# coBWeb.net
KiCad netlist of a schematic drawn in EasyEDA Pro
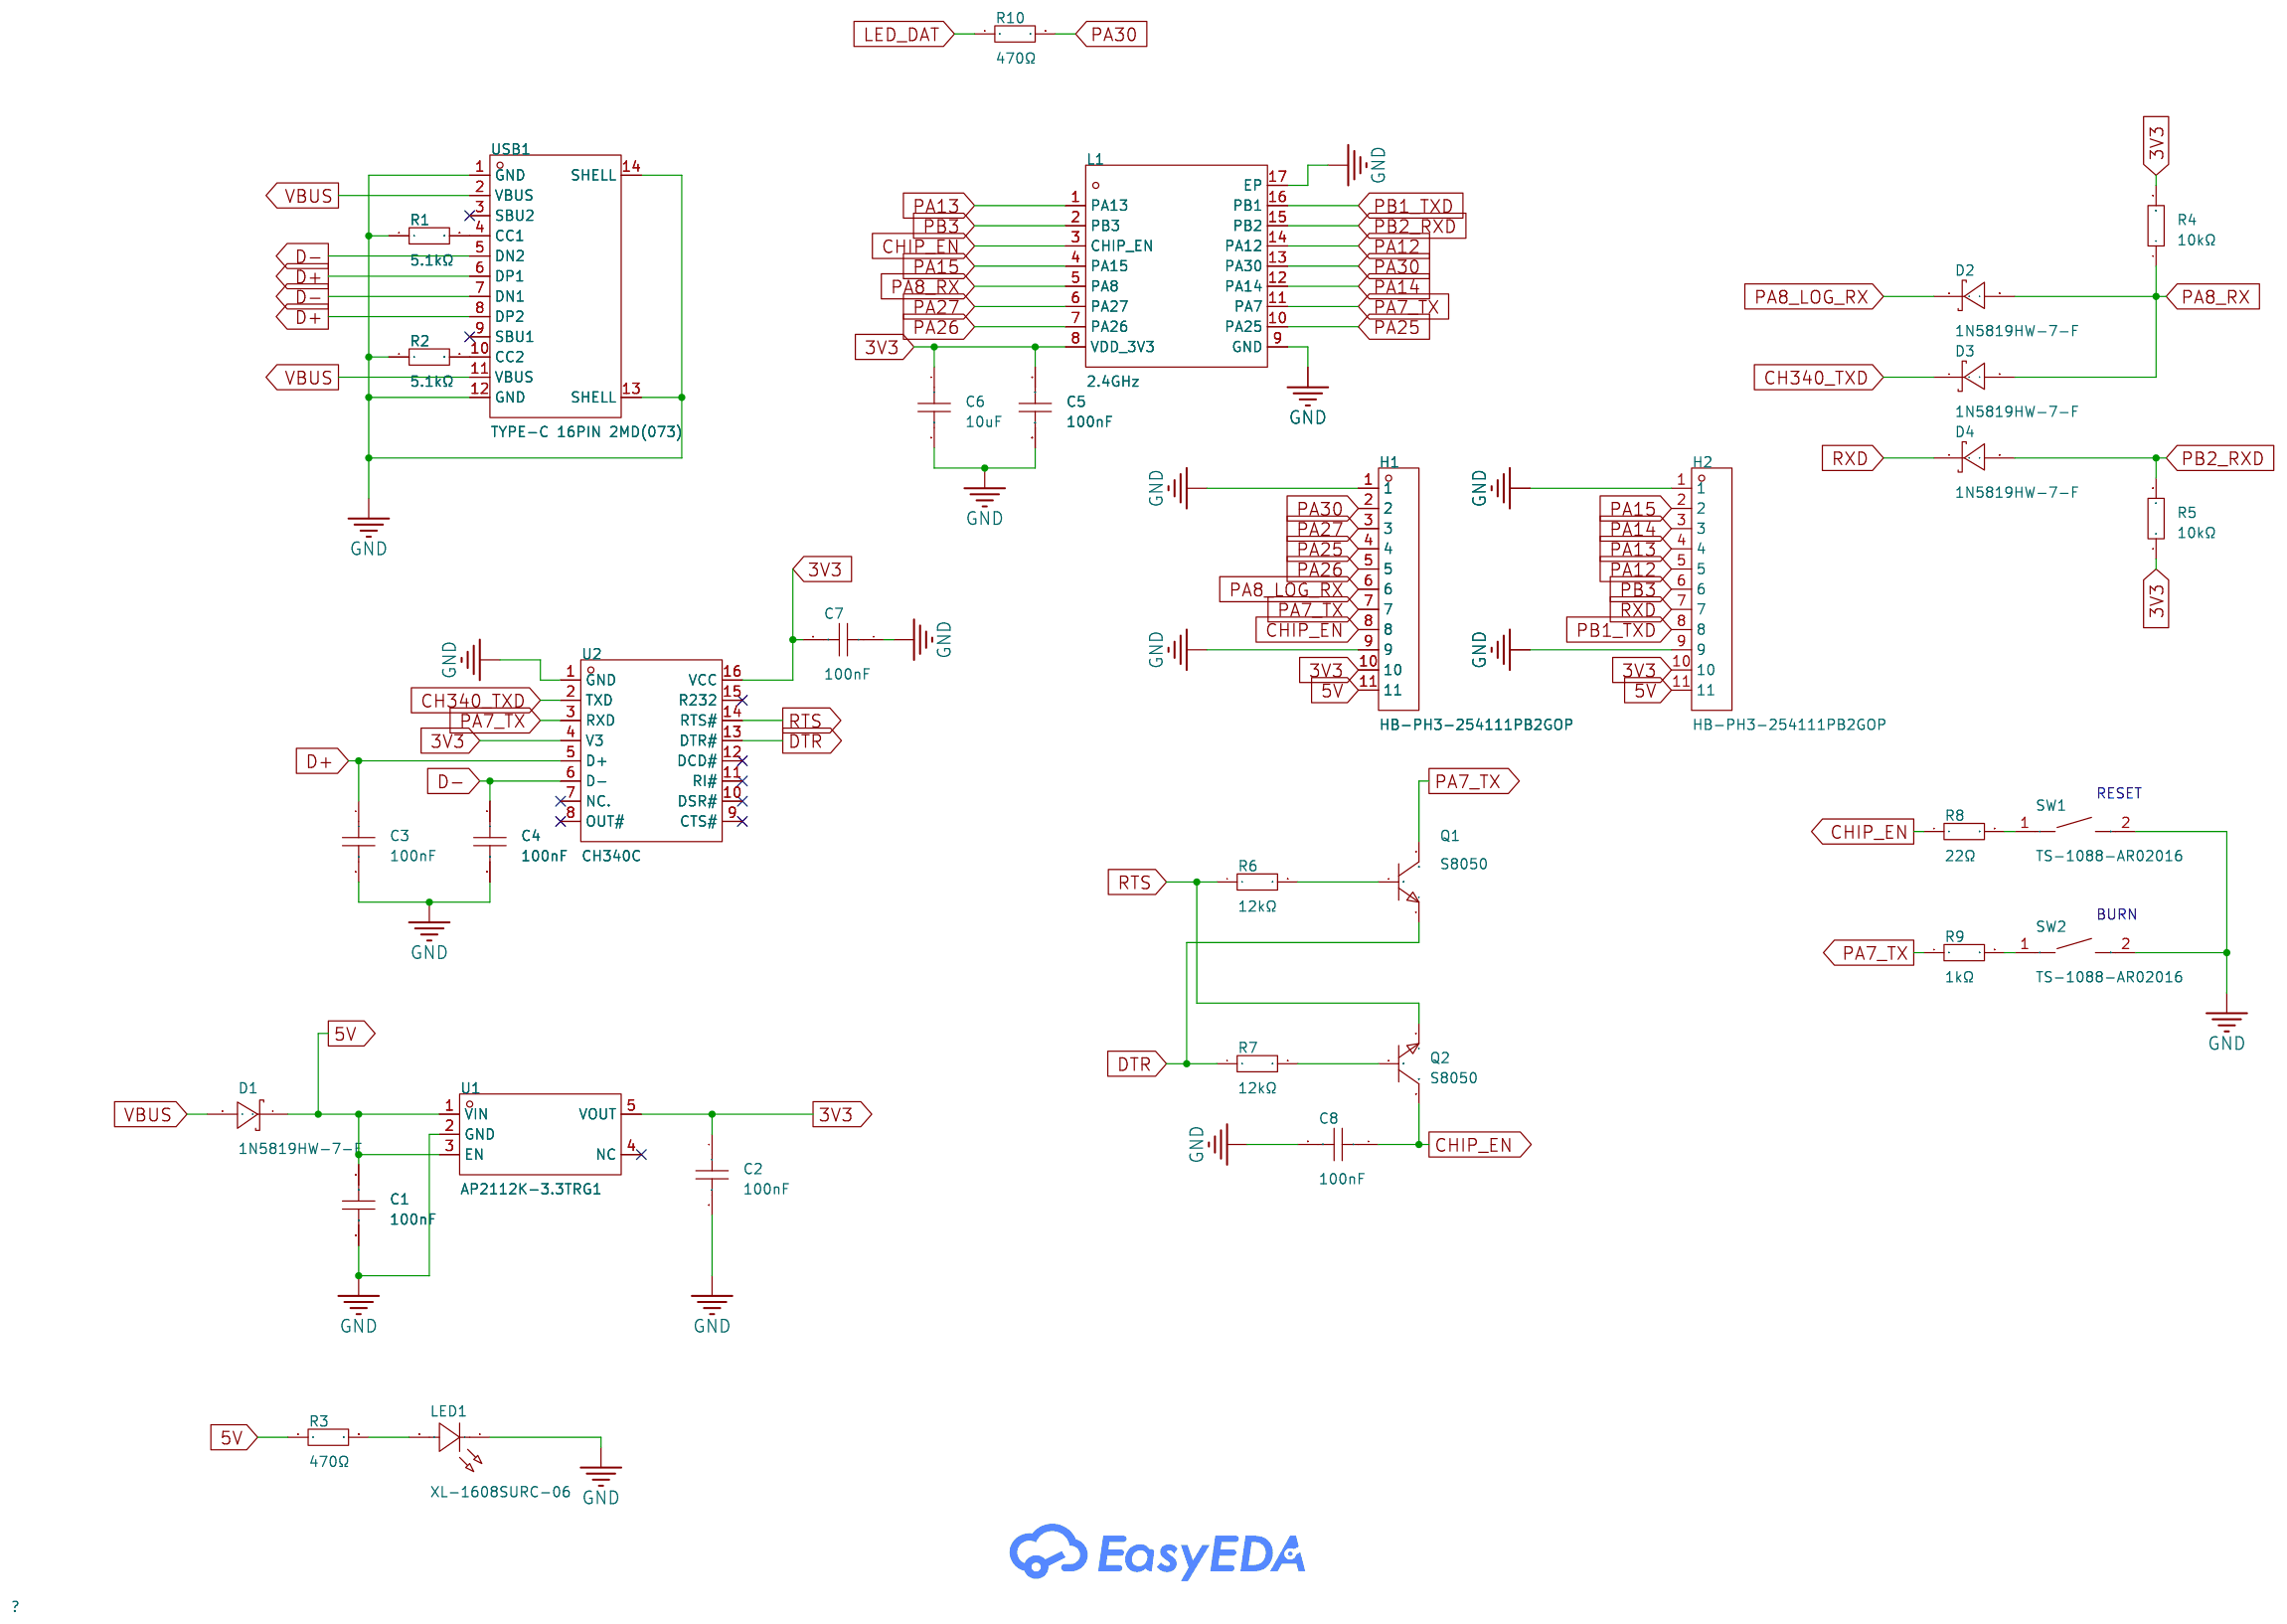
[diagram p0: P1]
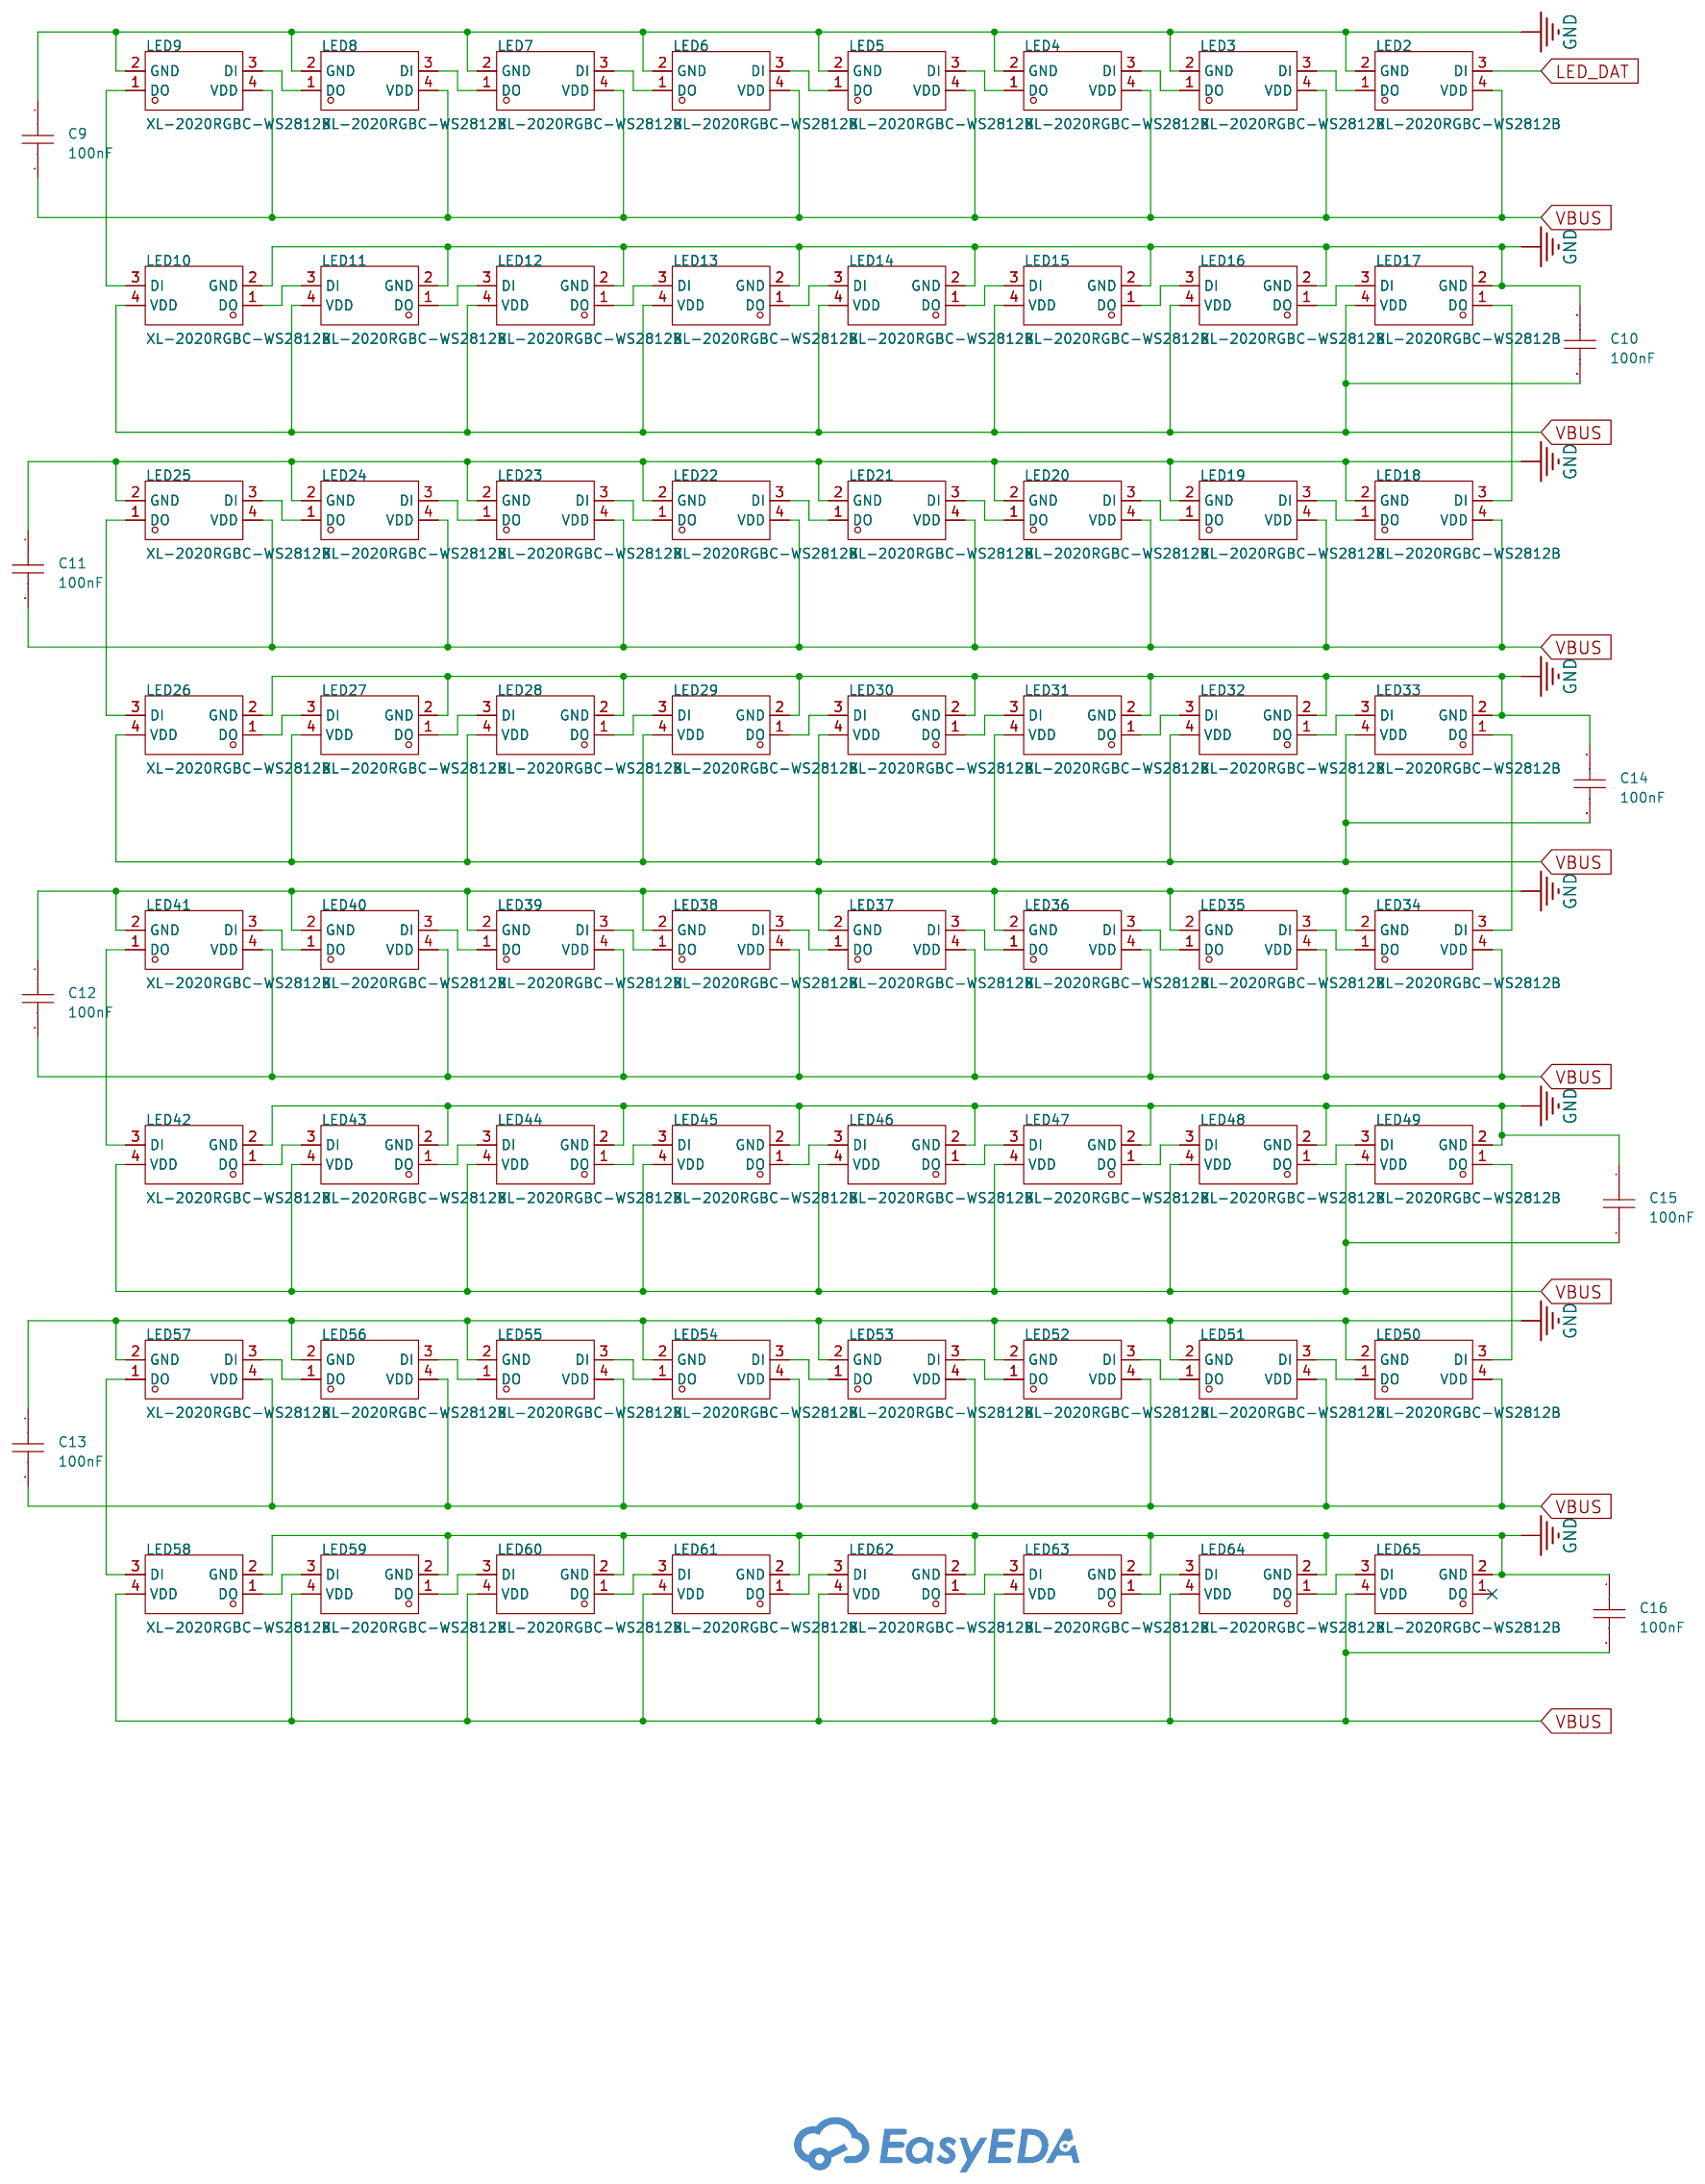
[diagram p1: P2]

(export (version "E")
  (design (tool "Eeschema 10.0.6"))
  (components
    (comp (ref "C1")
      (value "100nF")
      (footprint "easyedapro:C0603")
      (fields
        (field (name "Manufacturer Part") "CGA0402X7R104K160GT")
        (field (name "Manufacturer") "HRE(芯声)")
      )
      (libsource (lib "easyedapro") (part "CAP"))
    )
    (comp (ref "C2")
      (value "100nF")
      (footprint "easyedapro:C0603")
      (fields
        (field (name "Manufacturer Part") "CGA0402X7R104K160GT")
        (field (name "Manufacturer") "HRE(芯声)")
      )
      (libsource (lib "easyedapro") (part "CAP"))
    )
    (comp (ref "C3")
      (value "100nF")
      (footprint "easyedapro:C0603")
      (fields
        (field (name "Manufacturer Part") "CGA0402X7R104K160GT")
        (field (name "Manufacturer") "HRE(芯声)")
      )
      (libsource (lib "easyedapro") (part "CAP"))
    )
    (comp (ref "C4")
      (value "100nF")
      (footprint "easyedapro:C0603")
      (fields
        (field (name "Manufacturer Part") "CGA0402X7R104K160GT")
        (field (name "Manufacturer") "HRE(芯声)")
      )
      (libsource (lib "easyedapro") (part "CAP"))
    )
    (comp (ref "C5")
      (value "100nF")
      (footprint "easyedapro:C0603")
      (fields
        (field (name "Manufacturer Part") "CGA0402X7R104K160GT")
        (field (name "Manufacturer") "HRE(芯声)")
      )
      (libsource (lib "easyedapro") (part "CAP"))
    )
    (comp (ref "C6")
      (value "10uF")
      (footprint "easyedapro:C0603")
      (fields
        (field (name "Manufacturer Part") "GRM155R60J106ME44D")
        (field (name "Manufacturer") "muRata(村田)")
      )
      (libsource (lib "easyedapro") (part "CAP"))
    )
    (comp (ref "C7")
      (value "100nF")
      (footprint "easyedapro:C0603")
      (fields
        (field (name "Manufacturer Part") "CGA0402X7R104K160GT")
        (field (name "Manufacturer") "HRE(芯声)")
      )
      (libsource (lib "easyedapro") (part "CAP"))
    )
    (comp (ref "C8")
      (value "100nF")
      (footprint "easyedapro:C0603")
      (fields
        (field (name "Manufacturer Part") "CGA0402X7R104K160GT")
        (field (name "Manufacturer") "HRE(芯声)")
      )
      (libsource (lib "easyedapro") (part "CAP"))
    )
    (comp (ref "D1")
      (value "1N5819HW-7-F")
      (footprint "easyedapro:SOD-123_L2.7-W1.6-LS3.7-RD")
      (fields (field (name "Manufacturer") "DIODES(美台)"))
      (libsource (lib "easyedapro") (part "1N5819HW-7-F"))
    )
    (comp (ref "D2")
      (value "1N5819HW-7-F")
      (footprint "easyedapro:SOD-123_L2.7-W1.6-LS3.7-RD")
      (fields (field (name "Manufacturer") "DIODES(美台)"))
      (libsource (lib "easyedapro") (part "1N5819HW-7-F"))
    )
    (comp (ref "D3")
      (value "1N5819HW-7-F")
      (footprint "easyedapro:SOD-123_L2.7-W1.6-LS3.7-RD")
      (fields (field (name "Manufacturer") "DIODES(美台)"))
      (libsource (lib "easyedapro") (part "1N5819HW-7-F"))
    )
    (comp (ref "D4")
      (value "1N5819HW-7-F")
      (footprint "easyedapro:SOD-123_L2.7-W1.6-LS3.7-RD")
      (fields (field (name "Manufacturer") "DIODES(美台)"))
      (libsource (lib "easyedapro") (part "1N5819HW-7-F"))
    )
    (comp (ref "H1")
      (value "HB-PH3-254111PB2GOP")
      (footprint "easyedapro:HDR-TH_11P-P2.54-V-M")
      (fields (field (name "Manufacturer") "HANBO(汉博)"))
      (libsource (lib "easyedapro") (part "HB-PH3-254111PB2GOP"))
    )
    (comp (ref "H2")
      (value "HB-PH3-254111PB2GOP")
      (footprint "easyedapro:HDR-TH_11P-P2.54-V-M")
      (fields (field (name "Manufacturer") "HANBO(汉博)"))
      (libsource (lib "easyedapro") (part "HB-PH3-254111PB2GOP"))
    )
    (comp (ref "L1")
      (value "2.4GHz")
      (footprint "easyedapro:WIFI-SMD_BW16")
      (fields (field (name "Manufacturer Part") "BW16") (field (name "Manufacturer") "Ai-Thinker(安信可)"))
      (libsource (lib "easyedapro") (part "BW16"))
    )
    (comp (ref "LED1")
      (value "XL-1608SURC-06")
      (footprint "easyedapro:LED0603-RD_RED")
      (fields (field (name "Manufacturer") "XINGLIGHT(成兴光)"))
      (libsource (lib "easyedapro") (part "XL-1608SURC-06"))
    )
    (comp (ref "Q1")
      (value "S8050")
      (footprint "easyedapro:SOT-23-3_L2.9-W1.3-P1.90-LS2.4-BR")
      (fields (field (name "Manufacturer") "JSMSEMI(杰盛微)"))
      (libsource (lib "easyedapro") (part "S8050"))
    )
    (comp (ref "Q2")
      (value "S8050")
      (footprint "easyedapro:SOT-23-3_L2.9-W1.3-P1.90-LS2.4-BR")
      (fields (field (name "Manufacturer") "JSMSEMI(杰盛微)"))
      (libsource (lib "easyedapro") (part "S8050"))
    )
    (comp (ref "R1")
      (value "5.1kΩ")
      (footprint "easyedapro:R0603")
      (fields
        (field (name "Manufacturer Part") "0402WGF5101TCE")
        (field (name "Manufacturer") "UNI-ROYAL(厚声)")
      )
      (libsource (lib "easyedapro") (part "Res"))
    )
    (comp (ref "R2")
      (value "5.1kΩ")
      (footprint "easyedapro:R0603")
      (fields
        (field (name "Manufacturer Part") "0402WGF5101TCE")
        (field (name "Manufacturer") "UNI-ROYAL(厚声)")
      )
      (libsource (lib "easyedapro") (part "Res"))
    )
    (comp (ref "R3")
      (value "470Ω")
      (footprint "easyedapro:R0603")
      (fields (field (name "Manufacturer Part") "RC0402FR-07470RL") (field (name "Manufacturer") "YAGEO(国巨)"))
      (libsource (lib "easyedapro") (part "Res"))
    )
    (comp (ref "R4")
      (value "10kΩ")
      (footprint "easyedapro:R0603")
      (fields
        (field (name "Manufacturer Part") "0402WGF1002TCE")
        (field (name "Manufacturer") "UNI-ROYAL(厚声)")
      )
      (libsource (lib "easyedapro") (part "Res"))
    )
    (comp (ref "R5")
      (value "10kΩ")
      (footprint "easyedapro:R0603")
      (fields
        (field (name "Manufacturer Part") "0402WGF1002TCE")
        (field (name "Manufacturer") "UNI-ROYAL(厚声)")
      )
      (libsource (lib "easyedapro") (part "Res"))
    )
    (comp (ref "R6")
      (value "12kΩ")
      (footprint "easyedapro:R0603")
      (fields (field (name "Manufacturer Part") "RTT021202FTH") (field (name "Manufacturer") "RALEC(旺诠)"))
      (libsource (lib "easyedapro") (part "Res"))
    )
    (comp (ref "R7")
      (value "12kΩ")
      (footprint "easyedapro:R0603")
      (fields (field (name "Manufacturer Part") "RTT021202FTH") (field (name "Manufacturer") "RALEC(旺诠)"))
      (libsource (lib "easyedapro") (part "Res"))
    )
    (comp (ref "R8")
      (value "22Ω")
      (footprint "easyedapro:R0603")
      (fields
        (field (name "Manufacturer Part") "0402WGF220JTCE")
        (field (name "Manufacturer") "UNI-ROYAL(厚声)")
      )
      (libsource (lib "easyedapro") (part "Res"))
    )
    (comp (ref "R9")
      (value "1kΩ")
      (footprint "easyedapro:R0603")
      (fields
        (field (name "Manufacturer Part") "0402WGF1001TCE")
        (field (name "Manufacturer") "UNI-ROYAL(厚声)")
      )
      (libsource (lib "easyedapro") (part "Res"))
    )
    (comp (ref "R10")
      (value "470Ω")
      (footprint "easyedapro:R0603")
      (fields (field (name "Manufacturer Part") "RC0402FR-07470RL") (field (name "Manufacturer") "YAGEO(国巨)"))
      (libsource (lib "easyedapro") (part "Res"))
    )
    (comp (ref "SW1")
      (value "TS-1088-AR02016")
      (footprint "easyedapro:SW-SMD_L3.9-W3.0-P4.45")
      (fields (field (name "Manufacturer") "XUNPU(讯普)"))
      (libsource (lib "easyedapro") (part "TS-1088-AR02016"))
    )
    (comp (ref "SW2")
      (value "TS-1088-AR02016")
      (footprint "easyedapro:SW-SMD_L3.9-W3.0-P4.45")
      (fields (field (name "Manufacturer") "XUNPU(讯普)"))
      (libsource (lib "easyedapro") (part "TS-1088-AR02016"))
    )
    (comp (ref "U1")
      (value "AP2112K-3.3TRG1")
      (footprint "easyedapro:SOT-25-5_L2.9-W1.6-P0.95-LS2.8-BL")
      (fields (field (name "Manufacturer") "DIODES(美台)"))
      (libsource (lib "easyedapro") (part "AP2112K-3.3TRG1"))
    )
    (comp (ref "U2")
      (value "CH340C")
      (footprint "easyedapro:SOP-16_L10.0-W3.9-P1.27-LS6.0-BL")
      (fields (field (name "Manufacturer") "WCH(南京沁恒)"))
      (libsource (lib "easyedapro") (part "CH340C"))
    )
    (comp (ref "USB1")
      (value "TYPE-C 16PIN 2MD(073)")
      (footprint "easyedapro:USB-C-SMD_TYPE-C-6PIN-2MD-073")
      (fields (field (name "Manufacturer") "SHOU HAN(首韩)"))
      (libsource (lib "easyedapro") (part "TYPE-C 16PIN 2MD(073)"))
    )
    (comp (ref "C9")
      (value "100nF")
      (footprint "easyedapro:C0603")
      (fields
        (field (name "Manufacturer Part") "CGA0402X7R104K160GT")
        (field (name "Manufacturer") "HRE(芯声)")
      )
      (libsource (lib "easyedapro") (part "CAP"))
    )
    (comp (ref "C10")
      (value "100nF")
      (footprint "easyedapro:C0603")
      (fields
        (field (name "Manufacturer Part") "CGA0402X7R104K160GT")
        (field (name "Manufacturer") "HRE(芯声)")
      )
      (libsource (lib "easyedapro") (part "CAP"))
    )
    (comp (ref "C11")
      (value "100nF")
      (footprint "easyedapro:C0603")
      (fields
        (field (name "Manufacturer Part") "CGA0402X7R104K160GT")
        (field (name "Manufacturer") "HRE(芯声)")
      )
      (libsource (lib "easyedapro") (part "CAP"))
    )
    (comp (ref "C12")
      (value "100nF")
      (footprint "easyedapro:C0603")
      (fields
        (field (name "Manufacturer Part") "CGA0402X7R104K160GT")
        (field (name "Manufacturer") "HRE(芯声)")
      )
      (libsource (lib "easyedapro") (part "CAP"))
    )
    (comp (ref "C13")
      (value "100nF")
      (footprint "easyedapro:C0603")
      (fields
        (field (name "Manufacturer Part") "CGA0402X7R104K160GT")
        (field (name "Manufacturer") "HRE(芯声)")
      )
      (libsource (lib "easyedapro") (part "CAP"))
    )
    (comp (ref "C14")
      (value "100nF")
      (footprint "easyedapro:C0603")
      (fields
        (field (name "Manufacturer Part") "CGA0402X7R104K160GT")
        (field (name "Manufacturer") "HRE(芯声)")
      )
      (libsource (lib "easyedapro") (part "CAP"))
    )
    (comp (ref "C15")
      (value "100nF")
      (footprint "easyedapro:C0603")
      (fields
        (field (name "Manufacturer Part") "CGA0402X7R104K160GT")
        (field (name "Manufacturer") "HRE(芯声)")
      )
      (libsource (lib "easyedapro") (part "CAP"))
    )
    (comp (ref "C16")
      (value "100nF")
      (footprint "easyedapro:C0603")
      (fields
        (field (name "Manufacturer Part") "CGA0402X7R104K160GT")
        (field (name "Manufacturer") "HRE(芯声)")
      )
      (libsource (lib "easyedapro") (part "CAP"))
    )
    (comp (ref "LED2")
      (value "XL-2020RGBC-WS2812B")
      (footprint "easyedapro:LED-SMD_4P-L2.0-W2.0-BR-1")
      (fields (field (name "Manufacturer") "XINGLIGHT(成兴光)"))
      (libsource (lib "easyedapro") (part "XL-2020RGBC-WS2812B"))
    )
    (comp (ref "LED3")
      (value "XL-2020RGBC-WS2812B")
      (footprint "easyedapro:LED-SMD_4P-L2.0-W2.0-BR-1")
      (fields (field (name "Manufacturer") "XINGLIGHT(成兴光)"))
      (libsource (lib "easyedapro") (part "XL-2020RGBC-WS2812B"))
    )
    (comp (ref "LED4")
      (value "XL-2020RGBC-WS2812B")
      (footprint "easyedapro:LED-SMD_4P-L2.0-W2.0-BR-1")
      (fields (field (name "Manufacturer") "XINGLIGHT(成兴光)"))
      (libsource (lib "easyedapro") (part "XL-2020RGBC-WS2812B"))
    )
    (comp (ref "LED5")
      (value "XL-2020RGBC-WS2812B")
      (footprint "easyedapro:LED-SMD_4P-L2.0-W2.0-BR-1")
      (fields (field (name "Manufacturer") "XINGLIGHT(成兴光)"))
      (libsource (lib "easyedapro") (part "XL-2020RGBC-WS2812B"))
    )
    (comp (ref "LED6")
      (value "XL-2020RGBC-WS2812B")
      (footprint "easyedapro:LED-SMD_4P-L2.0-W2.0-BR-1")
      (fields (field (name "Manufacturer") "XINGLIGHT(成兴光)"))
      (libsource (lib "easyedapro") (part "XL-2020RGBC-WS2812B"))
    )
    (comp (ref "LED7")
      (value "XL-2020RGBC-WS2812B")
      (footprint "easyedapro:LED-SMD_4P-L2.0-W2.0-BR-1")
      (fields (field (name "Manufacturer") "XINGLIGHT(成兴光)"))
      (libsource (lib "easyedapro") (part "XL-2020RGBC-WS2812B"))
    )
    (comp (ref "LED8")
      (value "XL-2020RGBC-WS2812B")
      (footprint "easyedapro:LED-SMD_4P-L2.0-W2.0-BR-1")
      (fields (field (name "Manufacturer") "XINGLIGHT(成兴光)"))
      (libsource (lib "easyedapro") (part "XL-2020RGBC-WS2812B"))
    )
    (comp (ref "LED9")
      (value "XL-2020RGBC-WS2812B")
      (footprint "easyedapro:LED-SMD_4P-L2.0-W2.0-BR-1")
      (fields (field (name "Manufacturer") "XINGLIGHT(成兴光)"))
      (libsource (lib "easyedapro") (part "XL-2020RGBC-WS2812B"))
    )
    (comp (ref "LED10")
      (value "XL-2020RGBC-WS2812B")
      (footprint "easyedapro:LED-SMD_4P-L2.0-W2.0-BR-1")
      (fields (field (name "Manufacturer") "XINGLIGHT(成兴光)"))
      (libsource (lib "easyedapro") (part "XL-2020RGBC-WS2812B"))
    )
    (comp (ref "LED11")
      (value "XL-2020RGBC-WS2812B")
      (footprint "easyedapro:LED-SMD_4P-L2.0-W2.0-BR-1")
      (fields (field (name "Manufacturer") "XINGLIGHT(成兴光)"))
      (libsource (lib "easyedapro") (part "XL-2020RGBC-WS2812B"))
    )
    (comp (ref "LED12")
      (value "XL-2020RGBC-WS2812B")
      (footprint "easyedapro:LED-SMD_4P-L2.0-W2.0-BR-1")
      (fields (field (name "Manufacturer") "XINGLIGHT(成兴光)"))
      (libsource (lib "easyedapro") (part "XL-2020RGBC-WS2812B"))
    )
    (comp (ref "LED13")
      (value "XL-2020RGBC-WS2812B")
      (footprint "easyedapro:LED-SMD_4P-L2.0-W2.0-BR-1")
      (fields (field (name "Manufacturer") "XINGLIGHT(成兴光)"))
      (libsource (lib "easyedapro") (part "XL-2020RGBC-WS2812B"))
    )
    (comp (ref "LED14")
      (value "XL-2020RGBC-WS2812B")
      (footprint "easyedapro:LED-SMD_4P-L2.0-W2.0-BR-1")
      (fields (field (name "Manufacturer") "XINGLIGHT(成兴光)"))
      (libsource (lib "easyedapro") (part "XL-2020RGBC-WS2812B"))
    )
    (comp (ref "LED15")
      (value "XL-2020RGBC-WS2812B")
      (footprint "easyedapro:LED-SMD_4P-L2.0-W2.0-BR-1")
      (fields (field (name "Manufacturer") "XINGLIGHT(成兴光)"))
      (libsource (lib "easyedapro") (part "XL-2020RGBC-WS2812B"))
    )
    (comp (ref "LED16")
      (value "XL-2020RGBC-WS2812B")
      (footprint "easyedapro:LED-SMD_4P-L2.0-W2.0-BR-1")
      (fields (field (name "Manufacturer") "XINGLIGHT(成兴光)"))
      (libsource (lib "easyedapro") (part "XL-2020RGBC-WS2812B"))
    )
    (comp (ref "LED17")
      (value "XL-2020RGBC-WS2812B")
      (footprint "easyedapro:LED-SMD_4P-L2.0-W2.0-BR-1")
      (fields (field (name "Manufacturer") "XINGLIGHT(成兴光)"))
      (libsource (lib "easyedapro") (part "XL-2020RGBC-WS2812B"))
    )
    (comp (ref "LED18")
      (value "XL-2020RGBC-WS2812B")
      (footprint "easyedapro:LED-SMD_4P-L2.0-W2.0-BR-1")
      (fields (field (name "Manufacturer") "XINGLIGHT(成兴光)"))
      (libsource (lib "easyedapro") (part "XL-2020RGBC-WS2812B"))
    )
    (comp (ref "LED19")
      (value "XL-2020RGBC-WS2812B")
      (footprint "easyedapro:LED-SMD_4P-L2.0-W2.0-BR-1")
      (fields (field (name "Manufacturer") "XINGLIGHT(成兴光)"))
      (libsource (lib "easyedapro") (part "XL-2020RGBC-WS2812B"))
    )
    (comp (ref "LED20")
      (value "XL-2020RGBC-WS2812B")
      (footprint "easyedapro:LED-SMD_4P-L2.0-W2.0-BR-1")
      (fields (field (name "Manufacturer") "XINGLIGHT(成兴光)"))
      (libsource (lib "easyedapro") (part "XL-2020RGBC-WS2812B"))
    )
    (comp (ref "LED21")
      (value "XL-2020RGBC-WS2812B")
      (footprint "easyedapro:LED-SMD_4P-L2.0-W2.0-BR-1")
      (fields (field (name "Manufacturer") "XINGLIGHT(成兴光)"))
      (libsource (lib "easyedapro") (part "XL-2020RGBC-WS2812B"))
    )
    (comp (ref "LED22")
      (value "XL-2020RGBC-WS2812B")
      (footprint "easyedapro:LED-SMD_4P-L2.0-W2.0-BR-1")
      (fields (field (name "Manufacturer") "XINGLIGHT(成兴光)"))
      (libsource (lib "easyedapro") (part "XL-2020RGBC-WS2812B"))
    )
    (comp (ref "LED23")
      (value "XL-2020RGBC-WS2812B")
      (footprint "easyedapro:LED-SMD_4P-L2.0-W2.0-BR-1")
      (fields (field (name "Manufacturer") "XINGLIGHT(成兴光)"))
      (libsource (lib "easyedapro") (part "XL-2020RGBC-WS2812B"))
    )
    (comp (ref "LED24")
      (value "XL-2020RGBC-WS2812B")
      (footprint "easyedapro:LED-SMD_4P-L2.0-W2.0-BR-1")
      (fields (field (name "Manufacturer") "XINGLIGHT(成兴光)"))
      (libsource (lib "easyedapro") (part "XL-2020RGBC-WS2812B"))
    )
    (comp (ref "LED25")
      (value "XL-2020RGBC-WS2812B")
      (footprint "easyedapro:LED-SMD_4P-L2.0-W2.0-BR-1")
      (fields (field (name "Manufacturer") "XINGLIGHT(成兴光)"))
      (libsource (lib "easyedapro") (part "XL-2020RGBC-WS2812B"))
    )
    (comp (ref "LED26")
      (value "XL-2020RGBC-WS2812B")
      (footprint "easyedapro:LED-SMD_4P-L2.0-W2.0-BR-1")
      (fields (field (name "Manufacturer") "XINGLIGHT(成兴光)"))
      (libsource (lib "easyedapro") (part "XL-2020RGBC-WS2812B"))
    )
    (comp (ref "LED27")
      (value "XL-2020RGBC-WS2812B")
      (footprint "easyedapro:LED-SMD_4P-L2.0-W2.0-BR-1")
      (fields (field (name "Manufacturer") "XINGLIGHT(成兴光)"))
      (libsource (lib "easyedapro") (part "XL-2020RGBC-WS2812B"))
    )
    (comp (ref "LED28")
      (value "XL-2020RGBC-WS2812B")
      (footprint "easyedapro:LED-SMD_4P-L2.0-W2.0-BR-1")
      (fields (field (name "Manufacturer") "XINGLIGHT(成兴光)"))
      (libsource (lib "easyedapro") (part "XL-2020RGBC-WS2812B"))
    )
    (comp (ref "LED29")
      (value "XL-2020RGBC-WS2812B")
      (footprint "easyedapro:LED-SMD_4P-L2.0-W2.0-BR-1")
      (fields (field (name "Manufacturer") "XINGLIGHT(成兴光)"))
      (libsource (lib "easyedapro") (part "XL-2020RGBC-WS2812B"))
    )
    (comp (ref "LED30")
      (value "XL-2020RGBC-WS2812B")
      (footprint "easyedapro:LED-SMD_4P-L2.0-W2.0-BR-1")
      (fields (field (name "Manufacturer") "XINGLIGHT(成兴光)"))
      (libsource (lib "easyedapro") (part "XL-2020RGBC-WS2812B"))
    )
    (comp (ref "LED31")
      (value "XL-2020RGBC-WS2812B")
      (footprint "easyedapro:LED-SMD_4P-L2.0-W2.0-BR-1")
      (fields (field (name "Manufacturer") "XINGLIGHT(成兴光)"))
      (libsource (lib "easyedapro") (part "XL-2020RGBC-WS2812B"))
    )
    (comp (ref "LED32")
      (value "XL-2020RGBC-WS2812B")
      (footprint "easyedapro:LED-SMD_4P-L2.0-W2.0-BR-1")
      (fields (field (name "Manufacturer") "XINGLIGHT(成兴光)"))
      (libsource (lib "easyedapro") (part "XL-2020RGBC-WS2812B"))
    )
    (comp (ref "LED33")
      (value "XL-2020RGBC-WS2812B")
      (footprint "easyedapro:LED-SMD_4P-L2.0-W2.0-BR-1")
      (fields (field (name "Manufacturer") "XINGLIGHT(成兴光)"))
      (libsource (lib "easyedapro") (part "XL-2020RGBC-WS2812B"))
    )
    (comp (ref "LED34")
      (value "XL-2020RGBC-WS2812B")
      (footprint "easyedapro:LED-SMD_4P-L2.0-W2.0-BR-1")
      (fields (field (name "Manufacturer") "XINGLIGHT(成兴光)"))
      (libsource (lib "easyedapro") (part "XL-2020RGBC-WS2812B"))
    )
    (comp (ref "LED35")
      (value "XL-2020RGBC-WS2812B")
      (footprint "easyedapro:LED-SMD_4P-L2.0-W2.0-BR-1")
      (fields (field (name "Manufacturer") "XINGLIGHT(成兴光)"))
      (libsource (lib "easyedapro") (part "XL-2020RGBC-WS2812B"))
    )
    (comp (ref "LED36")
      (value "XL-2020RGBC-WS2812B")
      (footprint "easyedapro:LED-SMD_4P-L2.0-W2.0-BR-1")
      (fields (field (name "Manufacturer") "XINGLIGHT(成兴光)"))
      (libsource (lib "easyedapro") (part "XL-2020RGBC-WS2812B"))
    )
    (comp (ref "LED37")
      (value "XL-2020RGBC-WS2812B")
      (footprint "easyedapro:LED-SMD_4P-L2.0-W2.0-BR-1")
      (fields (field (name "Manufacturer") "XINGLIGHT(成兴光)"))
      (libsource (lib "easyedapro") (part "XL-2020RGBC-WS2812B"))
    )
    (comp (ref "LED38")
      (value "XL-2020RGBC-WS2812B")
      (footprint "easyedapro:LED-SMD_4P-L2.0-W2.0-BR-1")
      (fields (field (name "Manufacturer") "XINGLIGHT(成兴光)"))
      (libsource (lib "easyedapro") (part "XL-2020RGBC-WS2812B"))
    )
    (comp (ref "LED39")
      (value "XL-2020RGBC-WS2812B")
      (footprint "easyedapro:LED-SMD_4P-L2.0-W2.0-BR-1")
      (fields (field (name "Manufacturer") "XINGLIGHT(成兴光)"))
      (libsource (lib "easyedapro") (part "XL-2020RGBC-WS2812B"))
    )
    (comp (ref "LED40")
      (value "XL-2020RGBC-WS2812B")
      (footprint "easyedapro:LED-SMD_4P-L2.0-W2.0-BR-1")
      (fields (field (name "Manufacturer") "XINGLIGHT(成兴光)"))
      (libsource (lib "easyedapro") (part "XL-2020RGBC-WS2812B"))
    )
    (comp (ref "LED41")
      (value "XL-2020RGBC-WS2812B")
      (footprint "easyedapro:LED-SMD_4P-L2.0-W2.0-BR-1")
      (fields (field (name "Manufacturer") "XINGLIGHT(成兴光)"))
      (libsource (lib "easyedapro") (part "XL-2020RGBC-WS2812B"))
    )
    (comp (ref "LED42")
      (value "XL-2020RGBC-WS2812B")
      (footprint "easyedapro:LED-SMD_4P-L2.0-W2.0-BR-1")
      (fields (field (name "Manufacturer") "XINGLIGHT(成兴光)"))
      (libsource (lib "easyedapro") (part "XL-2020RGBC-WS2812B"))
    )
    (comp (ref "LED43")
      (value "XL-2020RGBC-WS2812B")
      (footprint "easyedapro:LED-SMD_4P-L2.0-W2.0-BR-1")
      (fields (field (name "Manufacturer") "XINGLIGHT(成兴光)"))
      (libsource (lib "easyedapro") (part "XL-2020RGBC-WS2812B"))
    )
    (comp (ref "LED44")
      (value "XL-2020RGBC-WS2812B")
      (footprint "easyedapro:LED-SMD_4P-L2.0-W2.0-BR-1")
      (fields (field (name "Manufacturer") "XINGLIGHT(成兴光)"))
      (libsource (lib "easyedapro") (part "XL-2020RGBC-WS2812B"))
    )
    (comp (ref "LED45")
      (value "XL-2020RGBC-WS2812B")
      (footprint "easyedapro:LED-SMD_4P-L2.0-W2.0-BR-1")
      (fields (field (name "Manufacturer") "XINGLIGHT(成兴光)"))
      (libsource (lib "easyedapro") (part "XL-2020RGBC-WS2812B"))
    )
    (comp (ref "LED46")
      (value "XL-2020RGBC-WS2812B")
      (footprint "easyedapro:LED-SMD_4P-L2.0-W2.0-BR-1")
      (fields (field (name "Manufacturer") "XINGLIGHT(成兴光)"))
      (libsource (lib "easyedapro") (part "XL-2020RGBC-WS2812B"))
    )
    (comp (ref "LED47")
      (value "XL-2020RGBC-WS2812B")
      (footprint "easyedapro:LED-SMD_4P-L2.0-W2.0-BR-1")
      (fields (field (name "Manufacturer") "XINGLIGHT(成兴光)"))
      (libsource (lib "easyedapro") (part "XL-2020RGBC-WS2812B"))
    )
    (comp (ref "LED48")
      (value "XL-2020RGBC-WS2812B")
      (footprint "easyedapro:LED-SMD_4P-L2.0-W2.0-BR-1")
      (fields (field (name "Manufacturer") "XINGLIGHT(成兴光)"))
      (libsource (lib "easyedapro") (part "XL-2020RGBC-WS2812B"))
    )
    (comp (ref "LED49")
      (value "XL-2020RGBC-WS2812B")
      (footprint "easyedapro:LED-SMD_4P-L2.0-W2.0-BR-1")
      (fields (field (name "Manufacturer") "XINGLIGHT(成兴光)"))
      (libsource (lib "easyedapro") (part "XL-2020RGBC-WS2812B"))
    )
    (comp (ref "LED50")
      (value "XL-2020RGBC-WS2812B")
      (footprint "easyedapro:LED-SMD_4P-L2.0-W2.0-BR-1")
      (fields (field (name "Manufacturer") "XINGLIGHT(成兴光)"))
      (libsource (lib "easyedapro") (part "XL-2020RGBC-WS2812B"))
    )
    (comp (ref "LED51")
      (value "XL-2020RGBC-WS2812B")
      (footprint "easyedapro:LED-SMD_4P-L2.0-W2.0-BR-1")
      (fields (field (name "Manufacturer") "XINGLIGHT(成兴光)"))
      (libsource (lib "easyedapro") (part "XL-2020RGBC-WS2812B"))
    )
    (comp (ref "LED52")
      (value "XL-2020RGBC-WS2812B")
      (footprint "easyedapro:LED-SMD_4P-L2.0-W2.0-BR-1")
      (fields (field (name "Manufacturer") "XINGLIGHT(成兴光)"))
      (libsource (lib "easyedapro") (part "XL-2020RGBC-WS2812B"))
    )
    (comp (ref "LED53")
      (value "XL-2020RGBC-WS2812B")
      (footprint "easyedapro:LED-SMD_4P-L2.0-W2.0-BR-1")
      (fields (field (name "Manufacturer") "XINGLIGHT(成兴光)"))
      (libsource (lib "easyedapro") (part "XL-2020RGBC-WS2812B"))
    )
    (comp (ref "LED54")
      (value "XL-2020RGBC-WS2812B")
      (footprint "easyedapro:LED-SMD_4P-L2.0-W2.0-BR-1")
      (fields (field (name "Manufacturer") "XINGLIGHT(成兴光)"))
      (libsource (lib "easyedapro") (part "XL-2020RGBC-WS2812B"))
    )
    (comp (ref "LED55")
      (value "XL-2020RGBC-WS2812B")
      (footprint "easyedapro:LED-SMD_4P-L2.0-W2.0-BR-1")
      (fields (field (name "Manufacturer") "XINGLIGHT(成兴光)"))
      (libsource (lib "easyedapro") (part "XL-2020RGBC-WS2812B"))
    )
    (comp (ref "LED56")
      (value "XL-2020RGBC-WS2812B")
      (footprint "easyedapro:LED-SMD_4P-L2.0-W2.0-BR-1")
      (fields (field (name "Manufacturer") "XINGLIGHT(成兴光)"))
      (libsource (lib "easyedapro") (part "XL-2020RGBC-WS2812B"))
    )
    (comp (ref "LED57")
      (value "XL-2020RGBC-WS2812B")
      (footprint "easyedapro:LED-SMD_4P-L2.0-W2.0-BR-1")
      (fields (field (name "Manufacturer") "XINGLIGHT(成兴光)"))
      (libsource (lib "easyedapro") (part "XL-2020RGBC-WS2812B"))
    )
    (comp (ref "LED58")
      (value "XL-2020RGBC-WS2812B")
      (footprint "easyedapro:LED-SMD_4P-L2.0-W2.0-BR-1")
      (fields (field (name "Manufacturer") "XINGLIGHT(成兴光)"))
      (libsource (lib "easyedapro") (part "XL-2020RGBC-WS2812B"))
    )
    (comp (ref "LED59")
      (value "XL-2020RGBC-WS2812B")
      (footprint "easyedapro:LED-SMD_4P-L2.0-W2.0-BR-1")
      (fields (field (name "Manufacturer") "XINGLIGHT(成兴光)"))
      (libsource (lib "easyedapro") (part "XL-2020RGBC-WS2812B"))
    )
    (comp (ref "LED60")
      (value "XL-2020RGBC-WS2812B")
      (footprint "easyedapro:LED-SMD_4P-L2.0-W2.0-BR-1")
      (fields (field (name "Manufacturer") "XINGLIGHT(成兴光)"))
      (libsource (lib "easyedapro") (part "XL-2020RGBC-WS2812B"))
    )
    (comp (ref "LED61")
      (value "XL-2020RGBC-WS2812B")
      (footprint "easyedapro:LED-SMD_4P-L2.0-W2.0-BR-1")
      (fields (field (name "Manufacturer") "XINGLIGHT(成兴光)"))
      (libsource (lib "easyedapro") (part "XL-2020RGBC-WS2812B"))
    )
    (comp (ref "LED62")
      (value "XL-2020RGBC-WS2812B")
      (footprint "easyedapro:LED-SMD_4P-L2.0-W2.0-BR-1")
      (fields (field (name "Manufacturer") "XINGLIGHT(成兴光)"))
      (libsource (lib "easyedapro") (part "XL-2020RGBC-WS2812B"))
    )
    (comp (ref "LED63")
      (value "XL-2020RGBC-WS2812B")
      (footprint "easyedapro:LED-SMD_4P-L2.0-W2.0-BR-1")
      (fields (field (name "Manufacturer") "XINGLIGHT(成兴光)"))
      (libsource (lib "easyedapro") (part "XL-2020RGBC-WS2812B"))
    )
    (comp (ref "LED64")
      (value "XL-2020RGBC-WS2812B")
      (footprint "easyedapro:LED-SMD_4P-L2.0-W2.0-BR-1")
      (fields (field (name "Manufacturer") "XINGLIGHT(成兴光)"))
      (libsource (lib "easyedapro") (part "XL-2020RGBC-WS2812B"))
    )
    (comp (ref "LED65")
      (value "XL-2020RGBC-WS2812B")
      (footprint "easyedapro:LED-SMD_4P-L2.0-W2.0-BR-1")
      (fields (field (name "Manufacturer") "XINGLIGHT(成兴光)"))
      (libsource (lib "easyedapro") (part "XL-2020RGBC-WS2812B"))
    )
  )
  (nets
    (net (code "1") (name "3V3") (class "Default")
      (node (ref "C2") (pin "1") (pinfunction "1_1") (pintype "input"))
      (node (ref "C5") (pin "1") (pinfunction "1_1") (pintype "input"))
      (node (ref "C6") (pin "1") (pinfunction "1_1") (pintype "input"))
      (node (ref "C7") (pin "2") (pinfunction "2_2") (pintype "input"))
      (node (ref "H1") (pin "10") (pinfunction "10_10") (pintype "unspecified"))
      (node (ref "H2") (pin "10") (pinfunction "10_10") (pintype "unspecified"))
      (node (ref "L1") (pin "8") (pinfunction "VDD_3V3_8") (pintype "unspecified"))
      (node (ref "R4") (pin "2") (pinfunction "2_2") (pintype "input"))
      (node (ref "R5") (pin "1") (pinfunction "1_1") (pintype "input"))
      (node (ref "U1") (pin "5") (pinfunction "VOUT_5") (pintype "unspecified"))
      (node (ref "U2") (pin "16") (pinfunction "VCC_16") (pintype "unspecified"))
      (node (ref "U2") (pin "4") (pinfunction "V3_4") (pintype "unspecified"))
    )
    (net (code "2") (name "5V") (class "Default")
      (node (ref "C1") (pin "1") (pinfunction "1_1") (pintype "input"))
      (node (ref "D1") (pin "1") (pinfunction "K_1") (pintype "unspecified"))
      (node (ref "H1") (pin "11") (pinfunction "11_11") (pintype "unspecified"))
      (node (ref "H2") (pin "11") (pinfunction "11_11") (pintype "unspecified"))
      (node (ref "R3") (pin "1") (pinfunction "1_1") (pintype "input"))
      (node (ref "U1") (pin "1") (pinfunction "VIN_1") (pintype "unspecified"))
      (node (ref "U1") (pin "3") (pinfunction "EN_3") (pintype "unspecified"))
    )
    (net (code "3") (name "CH340_TXD") (class "Default")
      (node (ref "D3") (pin "1") (pinfunction "K_1") (pintype "unspecified"))
      (node (ref "U2") (pin "2") (pinfunction "TXD_2") (pintype "unspecified"))
    )
    (net (code "4") (name "CHIP_EN") (class "Default")
      (node (ref "C8") (pin "1") (pinfunction "1_1") (pintype "input"))
      (node (ref "H1") (pin "8") (pinfunction "8_8") (pintype "unspecified"))
      (node (ref "L1") (pin "3") (pinfunction "CHIP_EN_3") (pintype "unspecified"))
      (node (ref "Q2") (pin "3") (pinfunction "C_3") (pintype "input"))
      (node (ref "R8") (pin "1") (pinfunction "1_1") (pintype "input"))
    )
    (net (code "5") (name "D+") (class "Default")
      (node (ref "C3") (pin "1") (pinfunction "1_1") (pintype "input"))
      (node (ref "U2") (pin "5") (pinfunction "D+_5") (pintype "unspecified"))
      (node (ref "USB1") (pin "6") (pinfunction "DP1_6") (pintype "unspecified"))
      (node (ref "USB1") (pin "8") (pinfunction "DP2_8") (pintype "unspecified"))
    )
    (net (code "6") (name "D-") (class "Default")
      (node (ref "C4") (pin "1") (pinfunction "1_1") (pintype "input"))
      (node (ref "U2") (pin "6") (pinfunction "D-_6") (pintype "unspecified"))
      (node (ref "USB1") (pin "5") (pinfunction "DN2_5") (pintype "unspecified"))
      (node (ref "USB1") (pin "7") (pinfunction "DN1_7") (pintype "unspecified"))
    )
    (net (code "7") (name "DTR") (class "Default")
      (node (ref "Q1") (pin "2") (pinfunction "E_2") (pintype "input"))
      (node (ref "R7") (pin "1") (pinfunction "1_1") (pintype "input"))
      (node (ref "U2") (pin "13") (pinfunction "DTR#_13") (pintype "unspecified"))
    )
    (net (code "8") (name "GND") (class "Default")
      (node (ref "C1") (pin "2") (pinfunction "2_2") (pintype "input"))
      (node (ref "C10") (pin "1") (pinfunction "1_1") (pintype "input"))
      (node (ref "C11") (pin "1") (pinfunction "1_1") (pintype "input"))
      (node (ref "C12") (pin "1") (pinfunction "1_1") (pintype "input"))
      (node (ref "C13") (pin "1") (pinfunction "1_1") (pintype "input"))
      (node (ref "C14") (pin "1") (pinfunction "1_1") (pintype "input"))
      (node (ref "C15") (pin "1") (pinfunction "1_1") (pintype "input"))
      (node (ref "C16") (pin "1") (pinfunction "1_1") (pintype "input"))
      (node (ref "C2") (pin "2") (pinfunction "2_2") (pintype "input"))
      (node (ref "C3") (pin "2") (pinfunction "2_2") (pintype "input"))
      (node (ref "C4") (pin "2") (pinfunction "2_2") (pintype "input"))
      (node (ref "C5") (pin "2") (pinfunction "2_2") (pintype "input"))
      (node (ref "C6") (pin "2") (pinfunction "2_2") (pintype "input"))
      (node (ref "C7") (pin "1") (pinfunction "1_1") (pintype "input"))
      (node (ref "C8") (pin "2") (pinfunction "2_2") (pintype "input"))
      (node (ref "C9") (pin "1") (pinfunction "1_1") (pintype "input"))
      (node (ref "H1") (pin "1") (pinfunction "1_1") (pintype "unspecified"))
      (node (ref "H1") (pin "9") (pinfunction "9_9") (pintype "unspecified"))
      (node (ref "H2") (pin "1") (pinfunction "1_1") (pintype "unspecified"))
      (node (ref "H2") (pin "9") (pinfunction "9_9") (pintype "unspecified"))
      (node (ref "L1") (pin "17") (pinfunction "EP_17") (pintype "unspecified"))
      (node (ref "L1") (pin "9") (pinfunction "GND_9") (pintype "unspecified"))
      (node (ref "LED1") (pin "1") (pinfunction "K_1") (pintype "unspecified"))
      (node (ref "LED10") (pin "2") (pinfunction "GND_2") (pintype "unspecified"))
      (node (ref "LED11") (pin "2") (pinfunction "GND_2") (pintype "unspecified"))
      (node (ref "LED12") (pin "2") (pinfunction "GND_2") (pintype "unspecified"))
      (node (ref "LED13") (pin "2") (pinfunction "GND_2") (pintype "unspecified"))
      (node (ref "LED14") (pin "2") (pinfunction "GND_2") (pintype "unspecified"))
      (node (ref "LED15") (pin "2") (pinfunction "GND_2") (pintype "unspecified"))
      (node (ref "LED16") (pin "2") (pinfunction "GND_2") (pintype "unspecified"))
      (node (ref "LED17") (pin "2") (pinfunction "GND_2") (pintype "unspecified"))
      (node (ref "LED18") (pin "2") (pinfunction "GND_2") (pintype "unspecified"))
      (node (ref "LED19") (pin "2") (pinfunction "GND_2") (pintype "unspecified"))
      (node (ref "LED2") (pin "2") (pinfunction "GND_2") (pintype "unspecified"))
      (node (ref "LED20") (pin "2") (pinfunction "GND_2") (pintype "unspecified"))
      (node (ref "LED21") (pin "2") (pinfunction "GND_2") (pintype "unspecified"))
      (node (ref "LED22") (pin "2") (pinfunction "GND_2") (pintype "unspecified"))
      (node (ref "LED23") (pin "2") (pinfunction "GND_2") (pintype "unspecified"))
      (node (ref "LED24") (pin "2") (pinfunction "GND_2") (pintype "unspecified"))
      (node (ref "LED25") (pin "2") (pinfunction "GND_2") (pintype "unspecified"))
      (node (ref "LED26") (pin "2") (pinfunction "GND_2") (pintype "unspecified"))
      (node (ref "LED27") (pin "2") (pinfunction "GND_2") (pintype "unspecified"))
      (node (ref "LED28") (pin "2") (pinfunction "GND_2") (pintype "unspecified"))
      (node (ref "LED29") (pin "2") (pinfunction "GND_2") (pintype "unspecified"))
      (node (ref "LED3") (pin "2") (pinfunction "GND_2") (pintype "unspecified"))
      (node (ref "LED30") (pin "2") (pinfunction "GND_2") (pintype "unspecified"))
      (node (ref "LED31") (pin "2") (pinfunction "GND_2") (pintype "unspecified"))
      (node (ref "LED32") (pin "2") (pinfunction "GND_2") (pintype "unspecified"))
      (node (ref "LED33") (pin "2") (pinfunction "GND_2") (pintype "unspecified"))
      (node (ref "LED34") (pin "2") (pinfunction "GND_2") (pintype "unspecified"))
      (node (ref "LED35") (pin "2") (pinfunction "GND_2") (pintype "unspecified"))
      (node (ref "LED36") (pin "2") (pinfunction "GND_2") (pintype "unspecified"))
      (node (ref "LED37") (pin "2") (pinfunction "GND_2") (pintype "unspecified"))
      (node (ref "LED38") (pin "2") (pinfunction "GND_2") (pintype "unspecified"))
      (node (ref "LED39") (pin "2") (pinfunction "GND_2") (pintype "unspecified"))
      (node (ref "LED4") (pin "2") (pinfunction "GND_2") (pintype "unspecified"))
      (node (ref "LED40") (pin "2") (pinfunction "GND_2") (pintype "unspecified"))
      (node (ref "LED41") (pin "2") (pinfunction "GND_2") (pintype "unspecified"))
      (node (ref "LED42") (pin "2") (pinfunction "GND_2") (pintype "unspecified"))
      (node (ref "LED43") (pin "2") (pinfunction "GND_2") (pintype "unspecified"))
      (node (ref "LED44") (pin "2") (pinfunction "GND_2") (pintype "unspecified"))
      (node (ref "LED45") (pin "2") (pinfunction "GND_2") (pintype "unspecified"))
      (node (ref "LED46") (pin "2") (pinfunction "GND_2") (pintype "unspecified"))
      (node (ref "LED47") (pin "2") (pinfunction "GND_2") (pintype "unspecified"))
      (node (ref "LED48") (pin "2") (pinfunction "GND_2") (pintype "unspecified"))
      (node (ref "LED49") (pin "2") (pinfunction "GND_2") (pintype "unspecified"))
      (node (ref "LED5") (pin "2") (pinfunction "GND_2") (pintype "unspecified"))
      (node (ref "LED50") (pin "2") (pinfunction "GND_2") (pintype "unspecified"))
      (node (ref "LED51") (pin "2") (pinfunction "GND_2") (pintype "unspecified"))
      (node (ref "LED52") (pin "2") (pinfunction "GND_2") (pintype "unspecified"))
      (node (ref "LED53") (pin "2") (pinfunction "GND_2") (pintype "unspecified"))
      (node (ref "LED54") (pin "2") (pinfunction "GND_2") (pintype "unspecified"))
      (node (ref "LED55") (pin "2") (pinfunction "GND_2") (pintype "unspecified"))
      (node (ref "LED56") (pin "2") (pinfunction "GND_2") (pintype "unspecified"))
      (node (ref "LED57") (pin "2") (pinfunction "GND_2") (pintype "unspecified"))
      (node (ref "LED58") (pin "2") (pinfunction "GND_2") (pintype "unspecified"))
      (node (ref "LED59") (pin "2") (pinfunction "GND_2") (pintype "unspecified"))
      (node (ref "LED6") (pin "2") (pinfunction "GND_2") (pintype "unspecified"))
      (node (ref "LED60") (pin "2") (pinfunction "GND_2") (pintype "unspecified"))
      (node (ref "LED61") (pin "2") (pinfunction "GND_2") (pintype "unspecified"))
      (node (ref "LED62") (pin "2") (pinfunction "GND_2") (pintype "unspecified"))
      (node (ref "LED63") (pin "2") (pinfunction "GND_2") (pintype "unspecified"))
      (node (ref "LED64") (pin "2") (pinfunction "GND_2") (pintype "unspecified"))
      (node (ref "LED65") (pin "2") (pinfunction "GND_2") (pintype "unspecified"))
      (node (ref "LED7") (pin "2") (pinfunction "GND_2") (pintype "unspecified"))
      (node (ref "LED8") (pin "2") (pinfunction "GND_2") (pintype "unspecified"))
      (node (ref "LED9") (pin "2") (pinfunction "GND_2") (pintype "unspecified"))
      (node (ref "R1") (pin "1") (pinfunction "1_1") (pintype "input"))
      (node (ref "R2") (pin "1") (pinfunction "1_1") (pintype "input"))
      (node (ref "SW1") (pin "2") (pinfunction "2_2") (pintype "unspecified"))
      (node (ref "SW2") (pin "2") (pinfunction "2_2") (pintype "unspecified"))
      (node (ref "U1") (pin "2") (pinfunction "GND_2") (pintype "unspecified"))
      (node (ref "U2") (pin "1") (pinfunction "GND_1") (pintype "unspecified"))
      (node (ref "USB1") (pin "1") (pinfunction "GND_1") (pintype "unspecified"))
      (node (ref "USB1") (pin "12") (pinfunction "GND_12") (pintype "unspecified"))
      (node (ref "USB1") (pin "13") (pinfunction "SHELL_13") (pintype "unspecified"))
      (node (ref "USB1") (pin "14") (pinfunction "SHELL_14") (pintype "unspecified"))
    )
    (net (code "9") (name "LED_DAT") (class "Default")
      (node (ref "LED2") (pin "3") (pinfunction "DI_3") (pintype "unspecified"))
      (node (ref "R10") (pin "1") (pinfunction "1_1") (pintype "input"))
    )
    (net (code "10") (name "Net-(LED1-A)") (class "Default")
      (node (ref "LED1") (pin "2") (pinfunction "A_2") (pintype "unspecified"))
      (node (ref "R3") (pin "2") (pinfunction "2_2") (pintype "input"))
    )
    (net (code "11") (name "Net-(LED2-DO)") (class "Default")
      (node (ref "LED2") (pin "1") (pinfunction "DO_1") (pintype "unspecified"))
      (node (ref "LED3") (pin "3") (pinfunction "DI_3") (pintype "unspecified"))
    )
    (net (code "12") (name "Net-(LED3-DO)") (class "Default")
      (node (ref "LED3") (pin "1") (pinfunction "DO_1") (pintype "unspecified"))
      (node (ref "LED4") (pin "3") (pinfunction "DI_3") (pintype "unspecified"))
    )
    (net (code "13") (name "Net-(LED4-DO)") (class "Default")
      (node (ref "LED4") (pin "1") (pinfunction "DO_1") (pintype "unspecified"))
      (node (ref "LED5") (pin "3") (pinfunction "DI_3") (pintype "unspecified"))
    )
    (net (code "14") (name "Net-(LED5-DO)") (class "Default")
      (node (ref "LED5") (pin "1") (pinfunction "DO_1") (pintype "unspecified"))
      (node (ref "LED6") (pin "3") (pinfunction "DI_3") (pintype "unspecified"))
    )
    (net (code "15") (name "Net-(LED6-DO)") (class "Default")
      (node (ref "LED6") (pin "1") (pinfunction "DO_1") (pintype "unspecified"))
      (node (ref "LED7") (pin "3") (pinfunction "DI_3") (pintype "unspecified"))
    )
    (net (code "16") (name "Net-(LED7-DO)") (class "Default")
      (node (ref "LED7") (pin "1") (pinfunction "DO_1") (pintype "unspecified"))
      (node (ref "LED8") (pin "3") (pinfunction "DI_3") (pintype "unspecified"))
    )
    (net (code "17") (name "Net-(LED8-DO)") (class "Default")
      (node (ref "LED8") (pin "1") (pinfunction "DO_1") (pintype "unspecified"))
      (node (ref "LED9") (pin "3") (pinfunction "DI_3") (pintype "unspecified"))
    )
    (net (code "18") (name "Net-(LED10-DI)") (class "Default")
      (node (ref "LED10") (pin "3") (pinfunction "DI_3") (pintype "unspecified"))
      (node (ref "LED9") (pin "1") (pinfunction "DO_1") (pintype "unspecified"))
    )
    (net (code "19") (name "Net-(LED10-DO)") (class "Default")
      (node (ref "LED10") (pin "1") (pinfunction "DO_1") (pintype "unspecified"))
      (node (ref "LED11") (pin "3") (pinfunction "DI_3") (pintype "unspecified"))
    )
    (net (code "20") (name "Net-(LED11-DO)") (class "Default")
      (node (ref "LED11") (pin "1") (pinfunction "DO_1") (pintype "unspecified"))
      (node (ref "LED12") (pin "3") (pinfunction "DI_3") (pintype "unspecified"))
    )
    (net (code "21") (name "Net-(LED12-DO)") (class "Default")
      (node (ref "LED12") (pin "1") (pinfunction "DO_1") (pintype "unspecified"))
      (node (ref "LED13") (pin "3") (pinfunction "DI_3") (pintype "unspecified"))
    )
    (net (code "22") (name "Net-(LED13-DO)") (class "Default")
      (node (ref "LED13") (pin "1") (pinfunction "DO_1") (pintype "unspecified"))
      (node (ref "LED14") (pin "3") (pinfunction "DI_3") (pintype "unspecified"))
    )
    (net (code "23") (name "Net-(LED14-DO)") (class "Default")
      (node (ref "LED14") (pin "1") (pinfunction "DO_1") (pintype "unspecified"))
      (node (ref "LED15") (pin "3") (pinfunction "DI_3") (pintype "unspecified"))
    )
    (net (code "24") (name "Net-(LED15-DO)") (class "Default")
      (node (ref "LED15") (pin "1") (pinfunction "DO_1") (pintype "unspecified"))
      (node (ref "LED16") (pin "3") (pinfunction "DI_3") (pintype "unspecified"))
    )
    (net (code "25") (name "Net-(LED16-DO)") (class "Default")
      (node (ref "LED16") (pin "1") (pinfunction "DO_1") (pintype "unspecified"))
      (node (ref "LED17") (pin "3") (pinfunction "DI_3") (pintype "unspecified"))
    )
    (net (code "26") (name "Net-(LED17-DO)") (class "Default")
      (node (ref "LED17") (pin "1") (pinfunction "DO_1") (pintype "unspecified"))
      (node (ref "LED18") (pin "3") (pinfunction "DI_3") (pintype "unspecified"))
    )
    (net (code "27") (name "Net-(LED18-DO)") (class "Default")
      (node (ref "LED18") (pin "1") (pinfunction "DO_1") (pintype "unspecified"))
      (node (ref "LED19") (pin "3") (pinfunction "DI_3") (pintype "unspecified"))
    )
    (net (code "28") (name "Net-(LED19-DO)") (class "Default")
      (node (ref "LED19") (pin "1") (pinfunction "DO_1") (pintype "unspecified"))
      (node (ref "LED20") (pin "3") (pinfunction "DI_3") (pintype "unspecified"))
    )
    (net (code "29") (name "Net-(LED20-DO)") (class "Default")
      (node (ref "LED20") (pin "1") (pinfunction "DO_1") (pintype "unspecified"))
      (node (ref "LED21") (pin "3") (pinfunction "DI_3") (pintype "unspecified"))
    )
    (net (code "30") (name "Net-(LED21-DO)") (class "Default")
      (node (ref "LED21") (pin "1") (pinfunction "DO_1") (pintype "unspecified"))
      (node (ref "LED22") (pin "3") (pinfunction "DI_3") (pintype "unspecified"))
    )
    (net (code "31") (name "Net-(LED22-DO)") (class "Default")
      (node (ref "LED22") (pin "1") (pinfunction "DO_1") (pintype "unspecified"))
      (node (ref "LED23") (pin "3") (pinfunction "DI_3") (pintype "unspecified"))
    )
    (net (code "32") (name "Net-(LED23-DO)") (class "Default")
      (node (ref "LED23") (pin "1") (pinfunction "DO_1") (pintype "unspecified"))
      (node (ref "LED24") (pin "3") (pinfunction "DI_3") (pintype "unspecified"))
    )
    (net (code "33") (name "Net-(LED24-DO)") (class "Default")
      (node (ref "LED24") (pin "1") (pinfunction "DO_1") (pintype "unspecified"))
      (node (ref "LED25") (pin "3") (pinfunction "DI_3") (pintype "unspecified"))
    )
    (net (code "34") (name "Net-(LED25-DO)") (class "Default")
      (node (ref "LED25") (pin "1") (pinfunction "DO_1") (pintype "unspecified"))
      (node (ref "LED26") (pin "3") (pinfunction "DI_3") (pintype "unspecified"))
    )
    (net (code "35") (name "Net-(LED26-DO)") (class "Default")
      (node (ref "LED26") (pin "1") (pinfunction "DO_1") (pintype "unspecified"))
      (node (ref "LED27") (pin "3") (pinfunction "DI_3") (pintype "unspecified"))
    )
    (net (code "36") (name "Net-(LED27-DO)") (class "Default")
      (node (ref "LED27") (pin "1") (pinfunction "DO_1") (pintype "unspecified"))
      (node (ref "LED28") (pin "3") (pinfunction "DI_3") (pintype "unspecified"))
    )
    (net (code "37") (name "Net-(LED28-DO)") (class "Default")
      (node (ref "LED28") (pin "1") (pinfunction "DO_1") (pintype "unspecified"))
      (node (ref "LED29") (pin "3") (pinfunction "DI_3") (pintype "unspecified"))
    )
    (net (code "38") (name "Net-(LED29-DO)") (class "Default")
      (node (ref "LED29") (pin "1") (pinfunction "DO_1") (pintype "unspecified"))
      (node (ref "LED30") (pin "3") (pinfunction "DI_3") (pintype "unspecified"))
    )
    (net (code "39") (name "Net-(LED30-DO)") (class "Default")
      (node (ref "LED30") (pin "1") (pinfunction "DO_1") (pintype "unspecified"))
      (node (ref "LED31") (pin "3") (pinfunction "DI_3") (pintype "unspecified"))
    )
    (net (code "40") (name "Net-(LED31-DO)") (class "Default")
      (node (ref "LED31") (pin "1") (pinfunction "DO_1") (pintype "unspecified"))
      (node (ref "LED32") (pin "3") (pinfunction "DI_3") (pintype "unspecified"))
    )
    (net (code "41") (name "Net-(LED32-DO)") (class "Default")
      (node (ref "LED32") (pin "1") (pinfunction "DO_1") (pintype "unspecified"))
      (node (ref "LED33") (pin "3") (pinfunction "DI_3") (pintype "unspecified"))
    )
    (net (code "42") (name "Net-(LED33-DO)") (class "Default")
      (node (ref "LED33") (pin "1") (pinfunction "DO_1") (pintype "unspecified"))
      (node (ref "LED34") (pin "3") (pinfunction "DI_3") (pintype "unspecified"))
    )
    (net (code "43") (name "Net-(LED34-DO)") (class "Default")
      (node (ref "LED34") (pin "1") (pinfunction "DO_1") (pintype "unspecified"))
      (node (ref "LED35") (pin "3") (pinfunction "DI_3") (pintype "unspecified"))
    )
    (net (code "44") (name "Net-(LED35-DO)") (class "Default")
      (node (ref "LED35") (pin "1") (pinfunction "DO_1") (pintype "unspecified"))
      (node (ref "LED36") (pin "3") (pinfunction "DI_3") (pintype "unspecified"))
    )
    (net (code "45") (name "Net-(LED36-DO)") (class "Default")
      (node (ref "LED36") (pin "1") (pinfunction "DO_1") (pintype "unspecified"))
      (node (ref "LED37") (pin "3") (pinfunction "DI_3") (pintype "unspecified"))
    )
    (net (code "46") (name "Net-(LED37-DO)") (class "Default")
      (node (ref "LED37") (pin "1") (pinfunction "DO_1") (pintype "unspecified"))
      (node (ref "LED38") (pin "3") (pinfunction "DI_3") (pintype "unspecified"))
    )
    (net (code "47") (name "Net-(LED38-DO)") (class "Default")
      (node (ref "LED38") (pin "1") (pinfunction "DO_1") (pintype "unspecified"))
      (node (ref "LED39") (pin "3") (pinfunction "DI_3") (pintype "unspecified"))
    )
    (net (code "48") (name "Net-(LED39-DO)") (class "Default")
      (node (ref "LED39") (pin "1") (pinfunction "DO_1") (pintype "unspecified"))
      (node (ref "LED40") (pin "3") (pinfunction "DI_3") (pintype "unspecified"))
    )
    (net (code "49") (name "Net-(LED40-DO)") (class "Default")
      (node (ref "LED40") (pin "1") (pinfunction "DO_1") (pintype "unspecified"))
      (node (ref "LED41") (pin "3") (pinfunction "DI_3") (pintype "unspecified"))
    )
    (net (code "50") (name "Net-(LED41-DO)") (class "Default")
      (node (ref "LED41") (pin "1") (pinfunction "DO_1") (pintype "unspecified"))
      (node (ref "LED42") (pin "3") (pinfunction "DI_3") (pintype "unspecified"))
    )
    (net (code "51") (name "Net-(LED42-DO)") (class "Default")
      (node (ref "LED42") (pin "1") (pinfunction "DO_1") (pintype "unspecified"))
      (node (ref "LED43") (pin "3") (pinfunction "DI_3") (pintype "unspecified"))
    )
    (net (code "52") (name "Net-(LED43-DO)") (class "Default")
      (node (ref "LED43") (pin "1") (pinfunction "DO_1") (pintype "unspecified"))
      (node (ref "LED44") (pin "3") (pinfunction "DI_3") (pintype "unspecified"))
    )
    (net (code "53") (name "Net-(LED44-DO)") (class "Default")
      (node (ref "LED44") (pin "1") (pinfunction "DO_1") (pintype "unspecified"))
      (node (ref "LED45") (pin "3") (pinfunction "DI_3") (pintype "unspecified"))
    )
    (net (code "54") (name "Net-(LED45-DO)") (class "Default")
      (node (ref "LED45") (pin "1") (pinfunction "DO_1") (pintype "unspecified"))
      (node (ref "LED46") (pin "3") (pinfunction "DI_3") (pintype "unspecified"))
    )
    (net (code "55") (name "Net-(LED46-DO)") (class "Default")
      (node (ref "LED46") (pin "1") (pinfunction "DO_1") (pintype "unspecified"))
      (node (ref "LED47") (pin "3") (pinfunction "DI_3") (pintype "unspecified"))
    )
    (net (code "56") (name "Net-(LED47-DO)") (class "Default")
      (node (ref "LED47") (pin "1") (pinfunction "DO_1") (pintype "unspecified"))
      (node (ref "LED48") (pin "3") (pinfunction "DI_3") (pintype "unspecified"))
    )
    (net (code "57") (name "Net-(LED48-DO)") (class "Default")
      (node (ref "LED48") (pin "1") (pinfunction "DO_1") (pintype "unspecified"))
      (node (ref "LED49") (pin "3") (pinfunction "DI_3") (pintype "unspecified"))
    )
    (net (code "58") (name "Net-(LED49-DO)") (class "Default")
      (node (ref "LED49") (pin "1") (pinfunction "DO_1") (pintype "unspecified"))
      (node (ref "LED50") (pin "3") (pinfunction "DI_3") (pintype "unspecified"))
    )
    (net (code "59") (name "Net-(LED50-DO)") (class "Default")
      (node (ref "LED50") (pin "1") (pinfunction "DO_1") (pintype "unspecified"))
      (node (ref "LED51") (pin "3") (pinfunction "DI_3") (pintype "unspecified"))
    )
    (net (code "60") (name "Net-(LED51-DO)") (class "Default")
      (node (ref "LED51") (pin "1") (pinfunction "DO_1") (pintype "unspecified"))
      (node (ref "LED52") (pin "3") (pinfunction "DI_3") (pintype "unspecified"))
    )
    (net (code "61") (name "Net-(LED52-DO)") (class "Default")
      (node (ref "LED52") (pin "1") (pinfunction "DO_1") (pintype "unspecified"))
      (node (ref "LED53") (pin "3") (pinfunction "DI_3") (pintype "unspecified"))
    )
    (net (code "62") (name "Net-(LED53-DO)") (class "Default")
      (node (ref "LED53") (pin "1") (pinfunction "DO_1") (pintype "unspecified"))
      (node (ref "LED54") (pin "3") (pinfunction "DI_3") (pintype "unspecified"))
    )
    (net (code "63") (name "Net-(LED54-DO)") (class "Default")
      (node (ref "LED54") (pin "1") (pinfunction "DO_1") (pintype "unspecified"))
      (node (ref "LED55") (pin "3") (pinfunction "DI_3") (pintype "unspecified"))
    )
    (net (code "64") (name "Net-(LED55-DO)") (class "Default")
      (node (ref "LED55") (pin "1") (pinfunction "DO_1") (pintype "unspecified"))
      (node (ref "LED56") (pin "3") (pinfunction "DI_3") (pintype "unspecified"))
    )
    (net (code "65") (name "Net-(LED56-DO)") (class "Default")
      (node (ref "LED56") (pin "1") (pinfunction "DO_1") (pintype "unspecified"))
      (node (ref "LED57") (pin "3") (pinfunction "DI_3") (pintype "unspecified"))
    )
    (net (code "66") (name "Net-(LED57-DO)") (class "Default")
      (node (ref "LED57") (pin "1") (pinfunction "DO_1") (pintype "unspecified"))
      (node (ref "LED58") (pin "3") (pinfunction "DI_3") (pintype "unspecified"))
    )
    (net (code "67") (name "Net-(LED58-DO)") (class "Default")
      (node (ref "LED58") (pin "1") (pinfunction "DO_1") (pintype "unspecified"))
      (node (ref "LED59") (pin "3") (pinfunction "DI_3") (pintype "unspecified"))
    )
    (net (code "68") (name "Net-(LED59-DO)") (class "Default")
      (node (ref "LED59") (pin "1") (pinfunction "DO_1") (pintype "unspecified"))
      (node (ref "LED60") (pin "3") (pinfunction "DI_3") (pintype "unspecified"))
    )
    (net (code "69") (name "Net-(LED60-DO)") (class "Default")
      (node (ref "LED60") (pin "1") (pinfunction "DO_1") (pintype "unspecified"))
      (node (ref "LED61") (pin "3") (pinfunction "DI_3") (pintype "unspecified"))
    )
    (net (code "70") (name "Net-(LED61-DO)") (class "Default")
      (node (ref "LED61") (pin "1") (pinfunction "DO_1") (pintype "unspecified"))
      (node (ref "LED62") (pin "3") (pinfunction "DI_3") (pintype "unspecified"))
    )
    (net (code "71") (name "Net-(LED62-DO)") (class "Default")
      (node (ref "LED62") (pin "1") (pinfunction "DO_1") (pintype "unspecified"))
      (node (ref "LED63") (pin "3") (pinfunction "DI_3") (pintype "unspecified"))
    )
    (net (code "72") (name "Net-(LED63-DO)") (class "Default")
      (node (ref "LED63") (pin "1") (pinfunction "DO_1") (pintype "unspecified"))
      (node (ref "LED64") (pin "3") (pinfunction "DI_3") (pintype "unspecified"))
    )
    (net (code "73") (name "Net-(LED64-DO)") (class "Default")
      (node (ref "LED64") (pin "1") (pinfunction "DO_1") (pintype "unspecified"))
      (node (ref "LED65") (pin "3") (pinfunction "DI_3") (pintype "unspecified"))
    )
    (net (code "74") (name "Net-(Q1-B)") (class "Default")
      (node (ref "Q1") (pin "1") (pinfunction "B_1") (pintype "input"))
      (node (ref "R6") (pin "2") (pinfunction "2_2") (pintype "input"))
    )
    (net (code "75") (name "Net-(Q2-B)") (class "Default")
      (node (ref "Q2") (pin "1") (pinfunction "B_1") (pintype "input"))
      (node (ref "R7") (pin "2") (pinfunction "2_2") (pintype "input"))
    )
    (net (code "76") (name "Net-(R8-Pad2)") (class "Default")
      (node (ref "R8") (pin "2") (pinfunction "2_2") (pintype "input"))
      (node (ref "SW1") (pin "1") (pinfunction "1_1") (pintype "unspecified"))
    )
    (net (code "77") (name "Net-(R9-Pad2)") (class "Default")
      (node (ref "R9") (pin "2") (pinfunction "2_2") (pintype "input"))
      (node (ref "SW2") (pin "1") (pinfunction "1_1") (pintype "unspecified"))
    )
    (net (code "78") (name "Net-(USB1-CC1)") (class "Default")
      (node (ref "R1") (pin "2") (pinfunction "2_2") (pintype "input"))
      (node (ref "USB1") (pin "4") (pinfunction "CC1_4") (pintype "unspecified"))
    )
    (net (code "79") (name "Net-(USB1-CC2)") (class "Default")
      (node (ref "R2") (pin "2") (pinfunction "2_2") (pintype "input"))
      (node (ref "USB1") (pin "10") (pinfunction "CC2_10") (pintype "unspecified"))
    )
    (net (code "80") (name "PA7_TX") (class "Default")
      (node (ref "H1") (pin "7") (pinfunction "7_7") (pintype "unspecified"))
      (node (ref "L1") (pin "11") (pinfunction "PA7_11") (pintype "unspecified"))
      (node (ref "Q1") (pin "3") (pinfunction "C_3") (pintype "input"))
      (node (ref "R9") (pin "1") (pinfunction "1_1") (pintype "input"))
      (node (ref "U2") (pin "3") (pinfunction "RXD_3") (pintype "unspecified"))
    )
    (net (code "81") (name "PA8_LOG_RX") (class "Default")
      (node (ref "D2") (pin "1") (pinfunction "K_1") (pintype "unspecified"))
      (node (ref "H1") (pin "6") (pinfunction "6_6") (pintype "unspecified"))
    )
    (net (code "82") (name "PA8_RX") (class "Default")
      (node (ref "D2") (pin "2") (pinfunction "A_2") (pintype "unspecified"))
      (node (ref "D3") (pin "2") (pinfunction "A_2") (pintype "unspecified"))
      (node (ref "L1") (pin "5") (pinfunction "PA8_5") (pintype "unspecified"))
      (node (ref "R4") (pin "1") (pinfunction "1_1") (pintype "input"))
    )
    (net (code "83") (name "PA12") (class "Default")
      (node (ref "H2") (pin "5") (pinfunction "5_5") (pintype "unspecified"))
      (node (ref "L1") (pin "14") (pinfunction "PA12_14") (pintype "unspecified"))
    )
    (net (code "84") (name "PA13") (class "Default")
      (node (ref "H2") (pin "4") (pinfunction "4_4") (pintype "unspecified"))
      (node (ref "L1") (pin "1") (pinfunction "PA13_1") (pintype "unspecified"))
    )
    (net (code "85") (name "PA14") (class "Default")
      (node (ref "H2") (pin "3") (pinfunction "3_3") (pintype "unspecified"))
      (node (ref "L1") (pin "12") (pinfunction "PA14_12") (pintype "unspecified"))
    )
    (net (code "86") (name "PA15") (class "Default")
      (node (ref "H2") (pin "2") (pinfunction "2_2") (pintype "unspecified"))
      (node (ref "L1") (pin "4") (pinfunction "PA15_4") (pintype "unspecified"))
    )
    (net (code "87") (name "PA25") (class "Default")
      (node (ref "H1") (pin "4") (pinfunction "4_4") (pintype "unspecified"))
      (node (ref "L1") (pin "10") (pinfunction "PA25_10") (pintype "unspecified"))
    )
    (net (code "88") (name "PA26") (class "Default")
      (node (ref "H1") (pin "5") (pinfunction "5_5") (pintype "unspecified"))
      (node (ref "L1") (pin "7") (pinfunction "PA26_7") (pintype "unspecified"))
    )
    (net (code "89") (name "PA27") (class "Default")
      (node (ref "H1") (pin "3") (pinfunction "3_3") (pintype "unspecified"))
      (node (ref "L1") (pin "6") (pinfunction "PA27_6") (pintype "unspecified"))
    )
    (net (code "90") (name "PA30") (class "Default")
      (node (ref "H1") (pin "2") (pinfunction "2_2") (pintype "unspecified"))
      (node (ref "L1") (pin "13") (pinfunction "PA30_13") (pintype "unspecified"))
      (node (ref "R10") (pin "2") (pinfunction "2_2") (pintype "input"))
    )
    (net (code "91") (name "PB1_TXD") (class "Default")
      (node (ref "H2") (pin "8") (pinfunction "8_8") (pintype "unspecified"))
      (node (ref "L1") (pin "16") (pinfunction "PB1_16") (pintype "unspecified"))
    )
    (net (code "92") (name "PB2_RXD") (class "Default")
      (node (ref "D4") (pin "2") (pinfunction "A_2") (pintype "unspecified"))
      (node (ref "L1") (pin "15") (pinfunction "PB2_15") (pintype "unspecified"))
      (node (ref "R5") (pin "2") (pinfunction "2_2") (pintype "input"))
    )
    (net (code "93") (name "PB3") (class "Default")
      (node (ref "H2") (pin "6") (pinfunction "6_6") (pintype "unspecified"))
      (node (ref "L1") (pin "2") (pinfunction "PB3_2") (pintype "unspecified"))
    )
    (net (code "94") (name "RTS") (class "Default")
      (node (ref "Q2") (pin "2") (pinfunction "E_2") (pintype "input"))
      (node (ref "R6") (pin "1") (pinfunction "1_1") (pintype "input"))
      (node (ref "U2") (pin "14") (pinfunction "RTS#_14") (pintype "unspecified"))
    )
    (net (code "95") (name "RXD") (class "Default")
      (node (ref "D4") (pin "1") (pinfunction "K_1") (pintype "unspecified"))
      (node (ref "H2") (pin "7") (pinfunction "7_7") (pintype "unspecified"))
    )
    (net (code "96") (name "VBUS") (class "Default")
      (node (ref "C10") (pin "2") (pinfunction "2_2") (pintype "input"))
      (node (ref "C11") (pin "2") (pinfunction "2_2") (pintype "input"))
      (node (ref "C12") (pin "2") (pinfunction "2_2") (pintype "input"))
      (node (ref "C13") (pin "2") (pinfunction "2_2") (pintype "input"))
      (node (ref "C14") (pin "2") (pinfunction "2_2") (pintype "input"))
      (node (ref "C15") (pin "2") (pinfunction "2_2") (pintype "input"))
      (node (ref "C16") (pin "2") (pinfunction "2_2") (pintype "input"))
      (node (ref "C9") (pin "2") (pinfunction "2_2") (pintype "input"))
      (node (ref "D1") (pin "2") (pinfunction "A_2") (pintype "unspecified"))
      (node (ref "LED10") (pin "4") (pinfunction "VDD_4") (pintype "unspecified"))
      (node (ref "LED11") (pin "4") (pinfunction "VDD_4") (pintype "unspecified"))
      (node (ref "LED12") (pin "4") (pinfunction "VDD_4") (pintype "unspecified"))
      (node (ref "LED13") (pin "4") (pinfunction "VDD_4") (pintype "unspecified"))
      (node (ref "LED14") (pin "4") (pinfunction "VDD_4") (pintype "unspecified"))
      (node (ref "LED15") (pin "4") (pinfunction "VDD_4") (pintype "unspecified"))
      (node (ref "LED16") (pin "4") (pinfunction "VDD_4") (pintype "unspecified"))
      (node (ref "LED17") (pin "4") (pinfunction "VDD_4") (pintype "unspecified"))
      (node (ref "LED18") (pin "4") (pinfunction "VDD_4") (pintype "unspecified"))
      (node (ref "LED19") (pin "4") (pinfunction "VDD_4") (pintype "unspecified"))
      (node (ref "LED2") (pin "4") (pinfunction "VDD_4") (pintype "unspecified"))
      (node (ref "LED20") (pin "4") (pinfunction "VDD_4") (pintype "unspecified"))
      (node (ref "LED21") (pin "4") (pinfunction "VDD_4") (pintype "unspecified"))
      (node (ref "LED22") (pin "4") (pinfunction "VDD_4") (pintype "unspecified"))
      (node (ref "LED23") (pin "4") (pinfunction "VDD_4") (pintype "unspecified"))
      (node (ref "LED24") (pin "4") (pinfunction "VDD_4") (pintype "unspecified"))
      (node (ref "LED25") (pin "4") (pinfunction "VDD_4") (pintype "unspecified"))
      (node (ref "LED26") (pin "4") (pinfunction "VDD_4") (pintype "unspecified"))
      (node (ref "LED27") (pin "4") (pinfunction "VDD_4") (pintype "unspecified"))
      (node (ref "LED28") (pin "4") (pinfunction "VDD_4") (pintype "unspecified"))
      (node (ref "LED29") (pin "4") (pinfunction "VDD_4") (pintype "unspecified"))
      (node (ref "LED3") (pin "4") (pinfunction "VDD_4") (pintype "unspecified"))
      (node (ref "LED30") (pin "4") (pinfunction "VDD_4") (pintype "unspecified"))
      (node (ref "LED31") (pin "4") (pinfunction "VDD_4") (pintype "unspecified"))
      (node (ref "LED32") (pin "4") (pinfunction "VDD_4") (pintype "unspecified"))
      (node (ref "LED33") (pin "4") (pinfunction "VDD_4") (pintype "unspecified"))
      (node (ref "LED34") (pin "4") (pinfunction "VDD_4") (pintype "unspecified"))
      (node (ref "LED35") (pin "4") (pinfunction "VDD_4") (pintype "unspecified"))
      (node (ref "LED36") (pin "4") (pinfunction "VDD_4") (pintype "unspecified"))
      (node (ref "LED37") (pin "4") (pinfunction "VDD_4") (pintype "unspecified"))
      (node (ref "LED38") (pin "4") (pinfunction "VDD_4") (pintype "unspecified"))
      (node (ref "LED39") (pin "4") (pinfunction "VDD_4") (pintype "unspecified"))
      (node (ref "LED4") (pin "4") (pinfunction "VDD_4") (pintype "unspecified"))
      (node (ref "LED40") (pin "4") (pinfunction "VDD_4") (pintype "unspecified"))
      (node (ref "LED41") (pin "4") (pinfunction "VDD_4") (pintype "unspecified"))
      (node (ref "LED42") (pin "4") (pinfunction "VDD_4") (pintype "unspecified"))
      (node (ref "LED43") (pin "4") (pinfunction "VDD_4") (pintype "unspecified"))
      (node (ref "LED44") (pin "4") (pinfunction "VDD_4") (pintype "unspecified"))
      (node (ref "LED45") (pin "4") (pinfunction "VDD_4") (pintype "unspecified"))
      (node (ref "LED46") (pin "4") (pinfunction "VDD_4") (pintype "unspecified"))
      (node (ref "LED47") (pin "4") (pinfunction "VDD_4") (pintype "unspecified"))
      (node (ref "LED48") (pin "4") (pinfunction "VDD_4") (pintype "unspecified"))
      (node (ref "LED49") (pin "4") (pinfunction "VDD_4") (pintype "unspecified"))
      (node (ref "LED5") (pin "4") (pinfunction "VDD_4") (pintype "unspecified"))
      (node (ref "LED50") (pin "4") (pinfunction "VDD_4") (pintype "unspecified"))
      (node (ref "LED51") (pin "4") (pinfunction "VDD_4") (pintype "unspecified"))
      (node (ref "LED52") (pin "4") (pinfunction "VDD_4") (pintype "unspecified"))
      (node (ref "LED53") (pin "4") (pinfunction "VDD_4") (pintype "unspecified"))
      (node (ref "LED54") (pin "4") (pinfunction "VDD_4") (pintype "unspecified"))
      (node (ref "LED55") (pin "4") (pinfunction "VDD_4") (pintype "unspecified"))
      (node (ref "LED56") (pin "4") (pinfunction "VDD_4") (pintype "unspecified"))
      (node (ref "LED57") (pin "4") (pinfunction "VDD_4") (pintype "unspecified"))
      (node (ref "LED58") (pin "4") (pinfunction "VDD_4") (pintype "unspecified"))
      (node (ref "LED59") (pin "4") (pinfunction "VDD_4") (pintype "unspecified"))
      (node (ref "LED6") (pin "4") (pinfunction "VDD_4") (pintype "unspecified"))
      (node (ref "LED60") (pin "4") (pinfunction "VDD_4") (pintype "unspecified"))
      (node (ref "LED61") (pin "4") (pinfunction "VDD_4") (pintype "unspecified"))
      (node (ref "LED62") (pin "4") (pinfunction "VDD_4") (pintype "unspecified"))
      (node (ref "LED63") (pin "4") (pinfunction "VDD_4") (pintype "unspecified"))
      (node (ref "LED64") (pin "4") (pinfunction "VDD_4") (pintype "unspecified"))
      (node (ref "LED65") (pin "4") (pinfunction "VDD_4") (pintype "unspecified"))
      (node (ref "LED7") (pin "4") (pinfunction "VDD_4") (pintype "unspecified"))
      (node (ref "LED8") (pin "4") (pinfunction "VDD_4") (pintype "unspecified"))
      (node (ref "LED9") (pin "4") (pinfunction "VDD_4") (pintype "unspecified"))
      (node (ref "USB1") (pin "11") (pinfunction "VBUS_11") (pintype "unspecified"))
      (node (ref "USB1") (pin "2") (pinfunction "VBUS_2") (pintype "unspecified"))
    )
    (net (code "97") (name "unconnected-(LED65-DO-Pad1)") (class "Default")
      (node (ref "LED65") (pin "1") (pinfunction "DO_1") (pintype "unspecified+no_connect"))
    )
    (net (code "98") (name "unconnected-(U1-NC-Pad4)") (class "Default")
      (node (ref "U1") (pin "4") (pinfunction "NC_4") (pintype "unspecified+no_connect"))
    )
    (net (code "99") (name "unconnected-(U2-CTS#-Pad9)") (class "Default")
      (node (ref "U2") (pin "9") (pinfunction "CTS#_9") (pintype "unspecified+no_connect"))
    )
    (net (code "100") (name "unconnected-(U2-DCD#-Pad12)") (class "Default")
      (node (ref "U2") (pin "12") (pinfunction "DCD#_12") (pintype "unspecified+no_connect"))
    )
    (net (code "101") (name "unconnected-(U2-DSR#-Pad10)") (class "Default")
      (node (ref "U2") (pin "10") (pinfunction "DSR#_10") (pintype "unspecified+no_connect"))
    )
    (net (code "102") (name "unconnected-(U2-NC.-Pad7)") (class "Default")
      (node (ref "U2") (pin "7") (pinfunction "NC._7") (pintype "unspecified+no_connect"))
    )
    (net (code "103") (name "unconnected-(U2-OUT#-Pad8)") (class "Default")
      (node (ref "U2") (pin "8") (pinfunction "OUT#_8") (pintype "unspecified+no_connect"))
    )
    (net (code "104") (name "unconnected-(U2-R232-Pad15)") (class "Default")
      (node (ref "U2") (pin "15") (pinfunction "R232_15") (pintype "unspecified+no_connect"))
    )
    (net (code "105") (name "unconnected-(U2-RI#-Pad11)") (class "Default")
      (node (ref "U2") (pin "11") (pinfunction "RI#_11") (pintype "unspecified+no_connect"))
    )
    (net (code "106") (name "unconnected-(USB1-SBU1-Pad9)") (class "Default")
      (node (ref "USB1") (pin "9") (pinfunction "SBU1_9") (pintype "unspecified+no_connect"))
    )
    (net (code "107") (name "unconnected-(USB1-SBU2-Pad3)") (class "Default")
      (node (ref "USB1") (pin "3") (pinfunction "SBU2_3") (pintype "unspecified+no_connect"))
    )
  )
)
